# reg-board-1.net
KiCad netlist of a schematic drawn in EAGLE
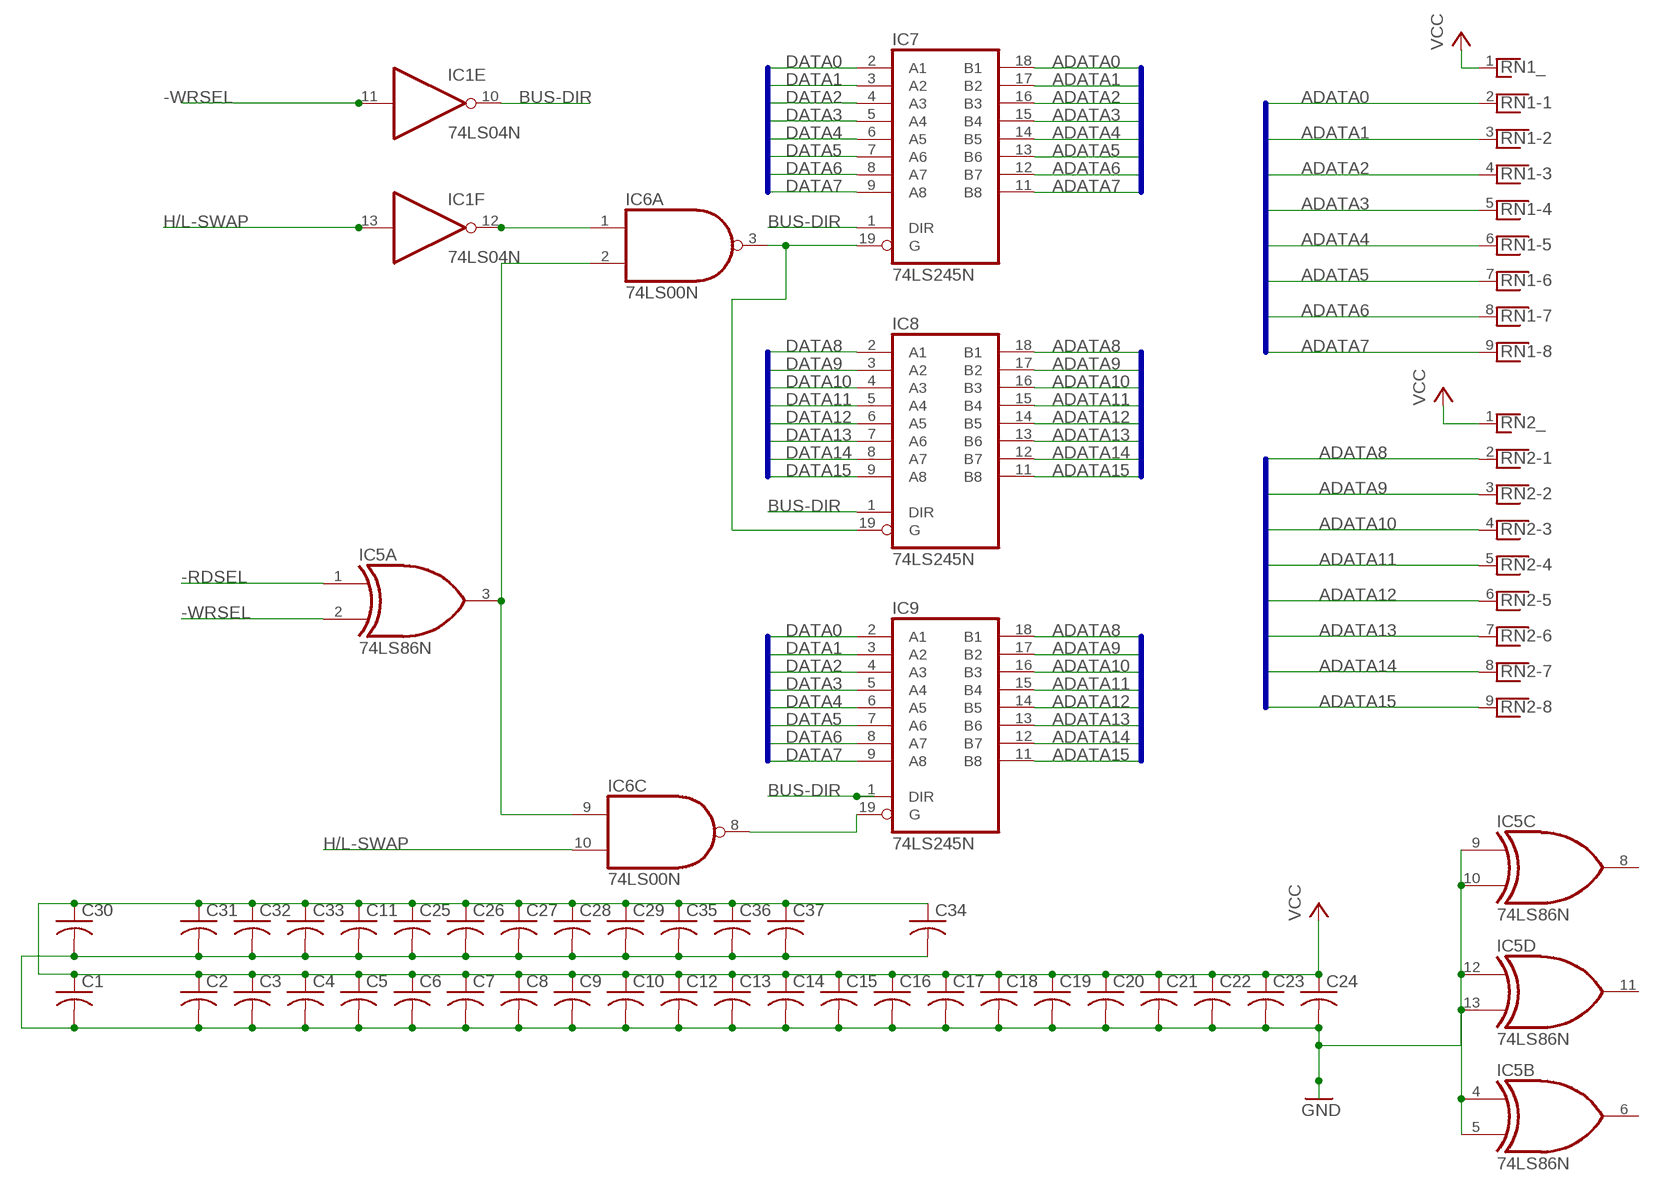
[diagram p0: schematic, sheet 1]
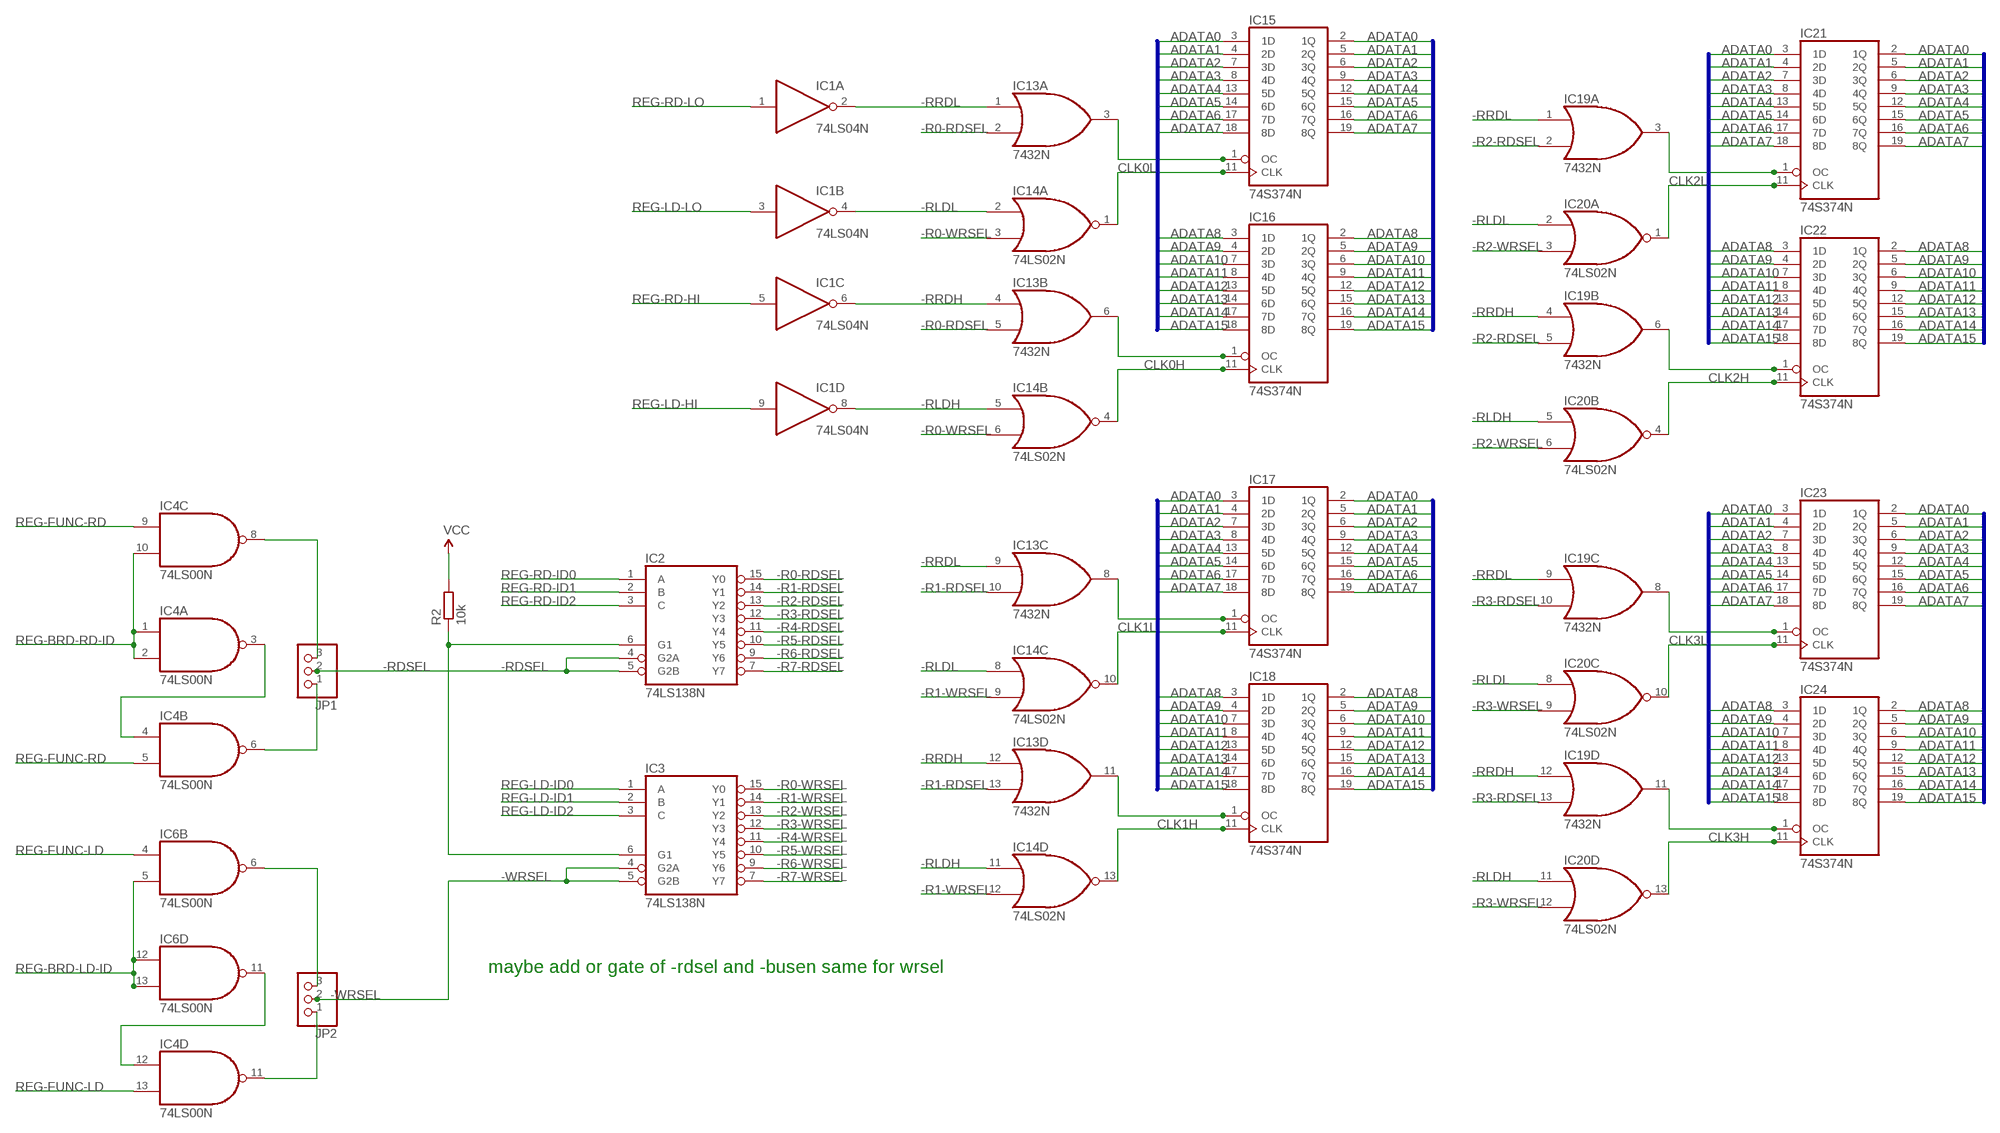
[diagram p1: schematic, sheet 2]
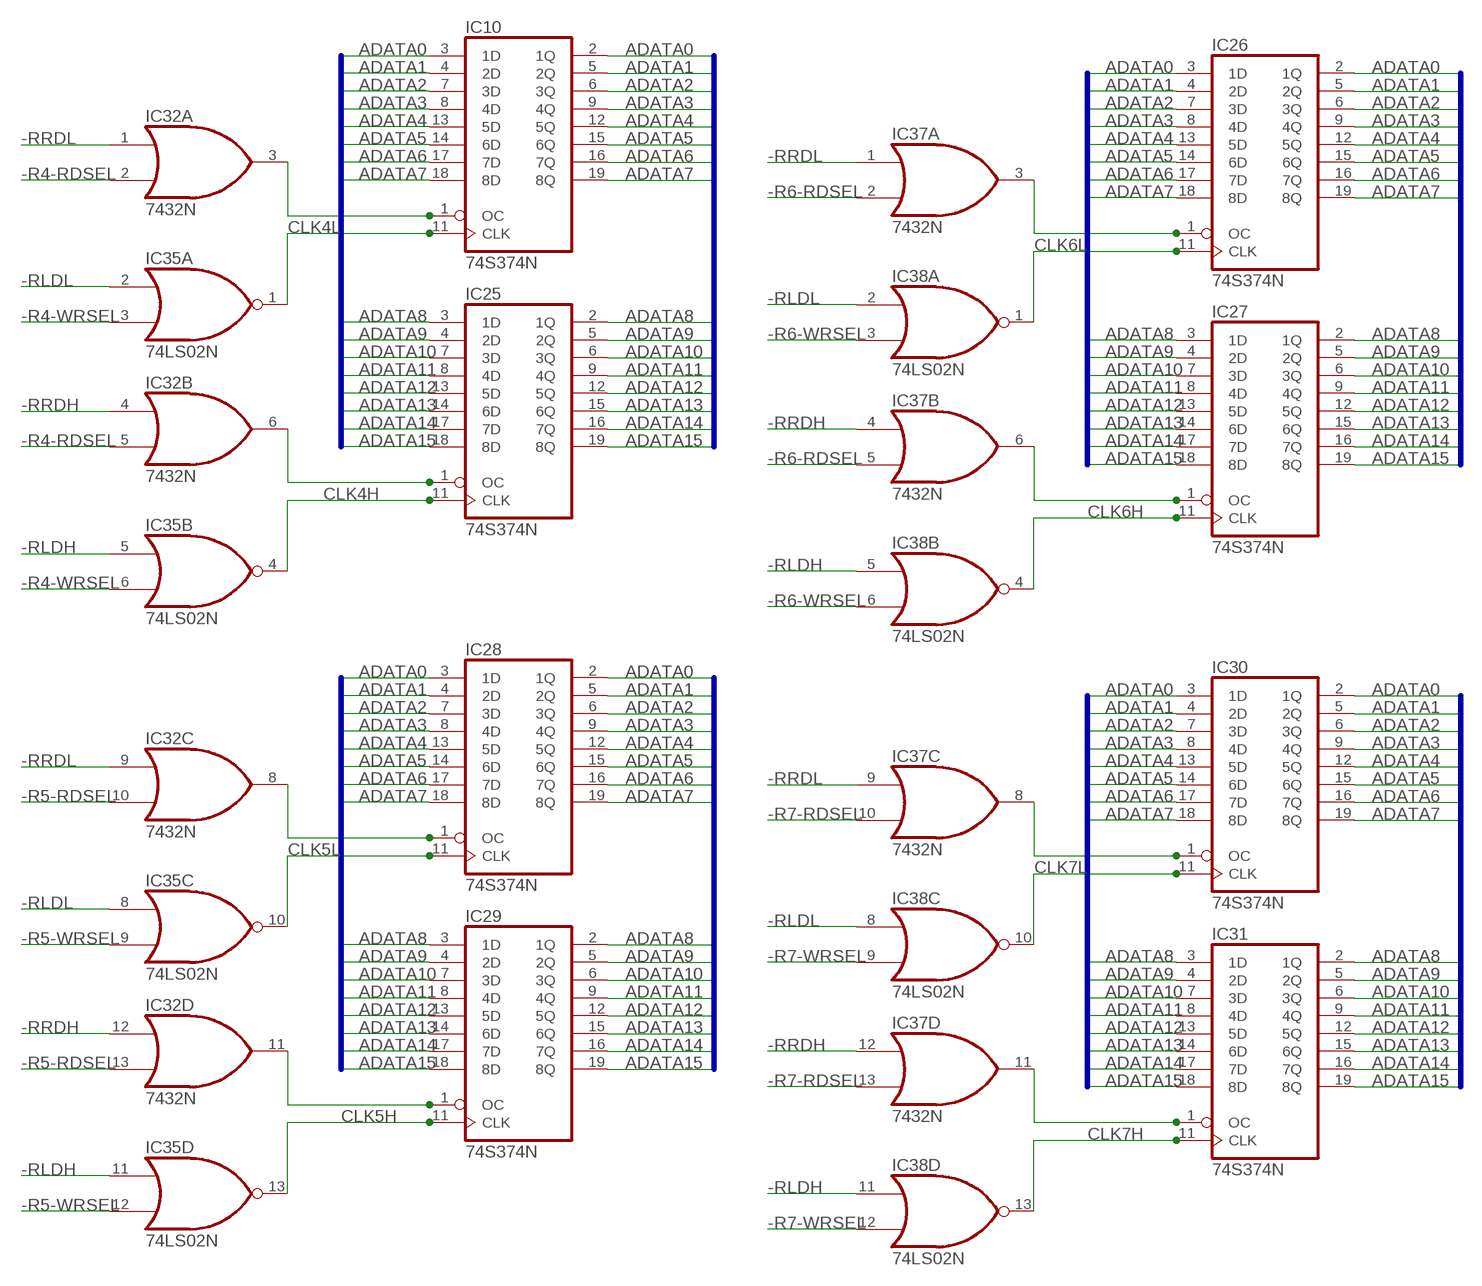
[diagram p2: schematic, sheet 3]
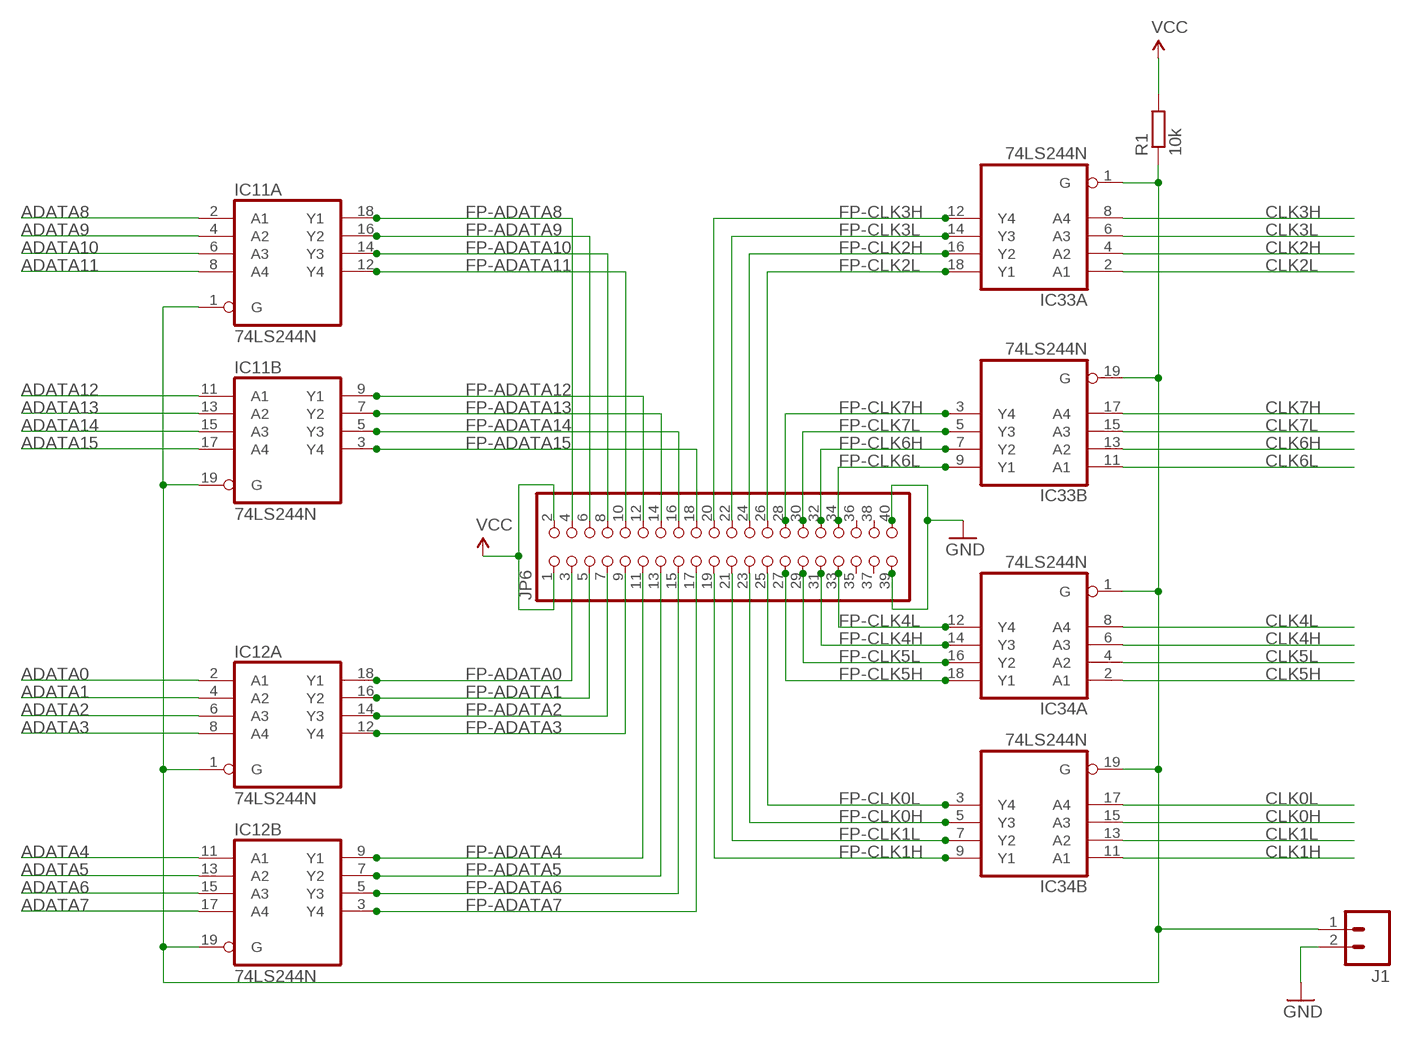
[diagram p3: schematic, sheet 4]
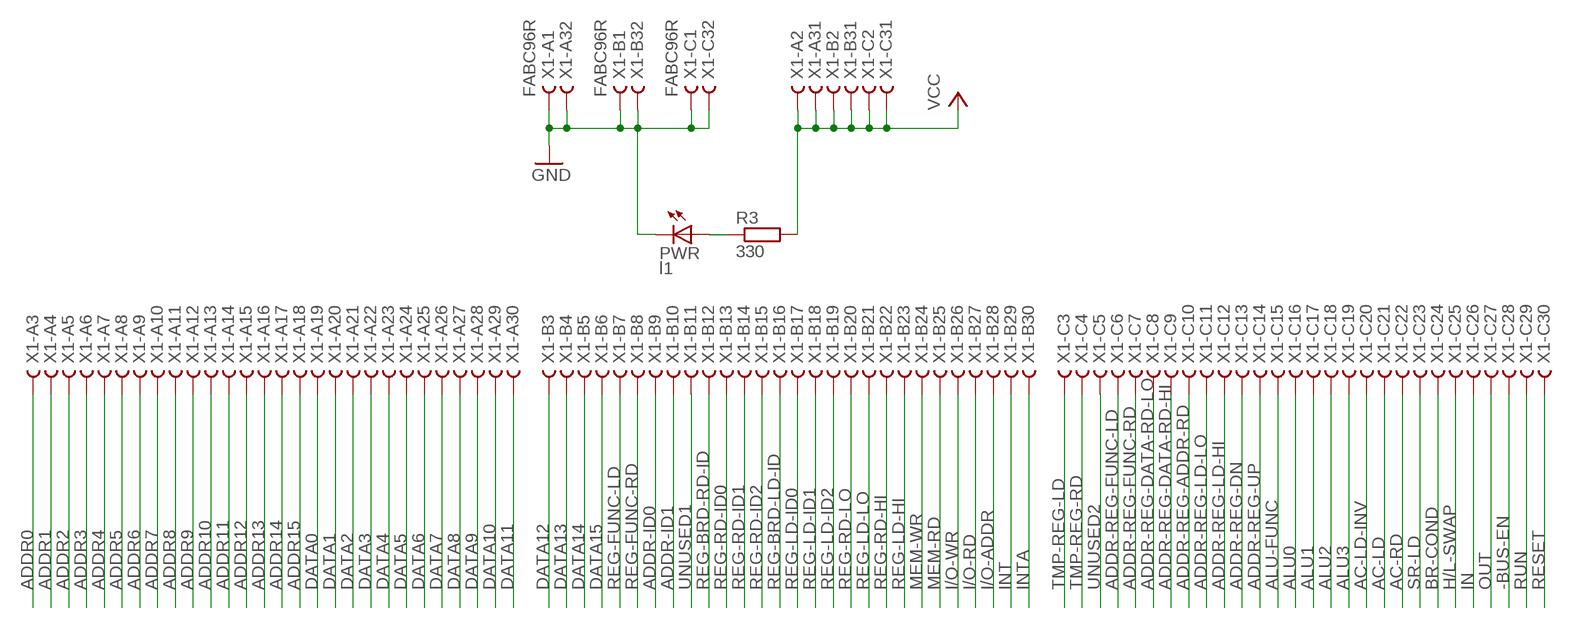
[diagram p4: schematic, sheet 5]

(export (version "E")
  (design (tool "Eeschema 10.0.6"))
  (components
    (comp (ref "IC10")
      (value "74S374N")
      (footprint "eagle-import:DIL20")
      (libsource (lib "eagle-import") (part "74374NS"))
    )
    (comp (ref "IC25")
      (value "74S374N")
      (footprint "eagle-import:DIL20")
      (libsource (lib "eagle-import") (part "74374NS"))
    )
    (comp (ref "IC26")
      (value "74S374N")
      (footprint "eagle-import:DIL20")
      (libsource (lib "eagle-import") (part "74374NS"))
    )
    (comp (ref "IC27")
      (value "74S374N")
      (footprint "eagle-import:DIL20")
      (libsource (lib "eagle-import") (part "74374NS"))
    )
    (comp (ref "IC28")
      (value "74S374N")
      (footprint "eagle-import:DIL20")
      (libsource (lib "eagle-import") (part "74374NS"))
    )
    (comp (ref "IC29")
      (value "74S374N")
      (footprint "eagle-import:DIL20")
      (libsource (lib "eagle-import") (part "74374NS"))
    )
    (comp (ref "IC30")
      (value "74S374N")
      (footprint "eagle-import:DIL20")
      (libsource (lib "eagle-import") (part "74374NS"))
    )
    (comp (ref "IC31")
      (value "74S374N")
      (footprint "eagle-import:DIL20")
      (libsource (lib "eagle-import") (part "74374NS"))
    )
    (comp (ref "IC32")
      (value "7432N")
      (footprint "eagle-import:DIL14")
      (libsource (lib "eagle-import") (part "7432N"))
    )
    (comp (ref "IC35")
      (value "74LS02N")
      (footprint "eagle-import:DIL14")
      (libsource (lib "eagle-import") (part "7402NLS"))
    )
    (comp (ref "IC37")
      (value "7432N")
      (footprint "eagle-import:DIL14")
      (libsource (lib "eagle-import") (part "7432N"))
    )
    (comp (ref "IC38")
      (value "74LS02N")
      (footprint "eagle-import:DIL14")
      (libsource (lib "eagle-import") (part "7402NLS"))
    )
    (comp (ref "IC1")
      (value "74LS04N")
      (footprint "eagle-import:DIL14")
      (libsource (lib "eagle-import") (part "7404NLS"))
    )
    (comp (ref "IC2")
      (value "74LS138N")
      (footprint "eagle-import:DIL16")
      (libsource (lib "eagle-import") (part "74138NLS"))
    )
    (comp (ref "IC3")
      (value "74LS138N")
      (footprint "eagle-import:DIL16")
      (libsource (lib "eagle-import") (part "74138NLS"))
    )
    (comp (ref "IC4")
      (value "74LS00N")
      (footprint "eagle-import:DIL14")
      (libsource (lib "eagle-import") (part "7400NLS"))
    )
    (comp (ref "IC6")
      (value "74LS00N")
      (footprint "eagle-import:DIL14")
      (libsource (lib "eagle-import") (part "7400NLS"))
    )
    (comp (ref "IC13")
      (value "7432N")
      (footprint "eagle-import:DIL14")
      (libsource (lib "eagle-import") (part "7432N"))
    )
    (comp (ref "IC14")
      (value "74LS02N")
      (footprint "eagle-import:DIL14")
      (libsource (lib "eagle-import") (part "7402NLS"))
    )
    (comp (ref "IC15")
      (value "74S374N")
      (footprint "eagle-import:DIL20")
      (libsource (lib "eagle-import") (part "74374NS"))
    )
    (comp (ref "IC16")
      (value "74S374N")
      (footprint "eagle-import:DIL20")
      (libsource (lib "eagle-import") (part "74374NS"))
    )
    (comp (ref "IC17")
      (value "74S374N")
      (footprint "eagle-import:DIL20")
      (libsource (lib "eagle-import") (part "74374NS"))
    )
    (comp (ref "IC18")
      (value "74S374N")
      (footprint "eagle-import:DIL20")
      (libsource (lib "eagle-import") (part "74374NS"))
    )
    (comp (ref "IC19")
      (value "7432N")
      (footprint "eagle-import:DIL14")
      (libsource (lib "eagle-import") (part "7432N"))
    )
    (comp (ref "IC20")
      (value "74LS02N")
      (footprint "eagle-import:DIL14")
      (libsource (lib "eagle-import") (part "7402NLS"))
    )
    (comp (ref "IC21")
      (value "74S374N")
      (footprint "eagle-import:DIL20")
      (libsource (lib "eagle-import") (part "74374NS"))
    )
    (comp (ref "IC22")
      (value "74S374N")
      (footprint "eagle-import:DIL20")
      (libsource (lib "eagle-import") (part "74374NS"))
    )
    (comp (ref "IC23")
      (value "74S374N")
      (footprint "eagle-import:DIL20")
      (libsource (lib "eagle-import") (part "74374NS"))
    )
    (comp (ref "IC24")
      (value "74S374N")
      (footprint "eagle-import:DIL20")
      (libsource (lib "eagle-import") (part "74374NS"))
    )
    (comp (ref "JP1")
      (value "PINHD-1X3")
      (footprint "eagle-import:1X03")
      (libsource (lib "eagle-import") (part "PINHD-1X3"))
    )
    (comp (ref "JP2")
      (value "PINHD-1X3")
      (footprint "eagle-import:1X03")
      (libsource (lib "eagle-import") (part "PINHD-1X3"))
    )
    (comp (ref "R2")
      (value "10k")
      (footprint "eagle-import:0207_10")
      (libsource (lib "eagle-import") (part "R0207/10"))
    )
    (comp (ref "PWR")
      (value "l1")
      (footprint "eagle-import:LED5MM")
      (libsource (lib "eagle-import") (part "LED5MM"))
    )
    (comp (ref "R3")
      (value "330")
      (footprint "eagle-import:0207_10")
      (libsource (lib "eagle-import") (part "R0207/10"))
    )
    (comp (ref "X1")
      (value "FABC96R")
      (footprint "eagle-import:FABC96R")
      (libsource (lib "eagle-import") (part "FABC96R"))
    )
    (comp (ref "IC11")
      (value "74LS244N")
      (footprint "eagle-import:DIL20")
      (libsource (lib "eagle-import") (part "74xx-us_74244NLS"))
    )
    (comp (ref "IC12")
      (value "74LS244N")
      (footprint "eagle-import:DIL20")
      (libsource (lib "eagle-import") (part "74xx-us_74244NLS"))
    )
    (comp (ref "IC33")
      (value "74LS244N")
      (footprint "eagle-import:DIL20")
      (libsource (lib "eagle-import") (part "74xx-us_74244NLS"))
    )
    (comp (ref "IC34")
      (value "74LS244N")
      (footprint "eagle-import:DIL20")
      (libsource (lib "eagle-import") (part "74xx-us_74244NLS"))
    )
    (comp (ref "J1")
      (value "M02PTH")
      (footprint "eagle-import:1X02")
      (libsource (lib "eagle-import") (part "M02PTH"))
    )
    (comp (ref "JP6")
      (value "PINHD-2X20")
      (footprint "eagle-import:2X20")
      (libsource (lib "eagle-import") (part "PINHD-2X20"))
    )
    (comp (ref "R1")
      (value "10k")
      (footprint "eagle-import:0207_10")
      (libsource (lib "eagle-import") (part "R0207/10"))
    )
    (comp (ref "C1")
      (value "C-US025-040X050")
      (footprint "eagle-import:C025-040X050")
      (libsource (lib "eagle-import") (part "C-US025-040X050"))
    )
    (comp (ref "C2")
      (value "C-US025-040X050")
      (footprint "eagle-import:C025-040X050")
      (libsource (lib "eagle-import") (part "C-US025-040X050"))
    )
    (comp (ref "C3")
      (value "C-US025-040X050")
      (footprint "eagle-import:C025-040X050")
      (libsource (lib "eagle-import") (part "C-US025-040X050"))
    )
    (comp (ref "C4")
      (value "C-US025-040X050")
      (footprint "eagle-import:C025-040X050")
      (libsource (lib "eagle-import") (part "C-US025-040X050"))
    )
    (comp (ref "C5")
      (value "C-US025-040X050")
      (footprint "eagle-import:C025-040X050")
      (libsource (lib "eagle-import") (part "C-US025-040X050"))
    )
    (comp (ref "C6")
      (value "C-US025-040X050")
      (footprint "eagle-import:C025-040X050")
      (libsource (lib "eagle-import") (part "C-US025-040X050"))
    )
    (comp (ref "C7")
      (value "C-US025-040X050")
      (footprint "eagle-import:C025-040X050")
      (libsource (lib "eagle-import") (part "C-US025-040X050"))
    )
    (comp (ref "C8")
      (value "C-US025-040X050")
      (footprint "eagle-import:C025-040X050")
      (libsource (lib "eagle-import") (part "C-US025-040X050"))
    )
    (comp (ref "C9")
      (value "C-US025-040X050")
      (footprint "eagle-import:C025-040X050")
      (libsource (lib "eagle-import") (part "C-US025-040X050"))
    )
    (comp (ref "C10")
      (value "C-US025-040X050")
      (footprint "eagle-import:C025-040X050")
      (libsource (lib "eagle-import") (part "C-US025-040X050"))
    )
    (comp (ref "C11")
      (value "C-US025-040X050")
      (footprint "eagle-import:C025-040X050")
      (libsource (lib "eagle-import") (part "C-US025-040X050"))
    )
    (comp (ref "C12")
      (value "C-US025-040X050")
      (footprint "eagle-import:C025-040X050")
      (libsource (lib "eagle-import") (part "C-US025-040X050"))
    )
    (comp (ref "C13")
      (value "C-US025-040X050")
      (footprint "eagle-import:C025-040X050")
      (libsource (lib "eagle-import") (part "C-US025-040X050"))
    )
    (comp (ref "C14")
      (value "C-US025-040X050")
      (footprint "eagle-import:C025-040X050")
      (libsource (lib "eagle-import") (part "C-US025-040X050"))
    )
    (comp (ref "C15")
      (value "C-US025-040X050")
      (footprint "eagle-import:C025-040X050")
      (libsource (lib "eagle-import") (part "C-US025-040X050"))
    )
    (comp (ref "C16")
      (value "C-US025-040X050")
      (footprint "eagle-import:C025-040X050")
      (libsource (lib "eagle-import") (part "C-US025-040X050"))
    )
    (comp (ref "C17")
      (value "C-US025-040X050")
      (footprint "eagle-import:C025-040X050")
      (libsource (lib "eagle-import") (part "C-US025-040X050"))
    )
    (comp (ref "C18")
      (value "C-US025-040X050")
      (footprint "eagle-import:C025-040X050")
      (libsource (lib "eagle-import") (part "C-US025-040X050"))
    )
    (comp (ref "C19")
      (value "C-US025-040X050")
      (footprint "eagle-import:C025-040X050")
      (libsource (lib "eagle-import") (part "C-US025-040X050"))
    )
    (comp (ref "C20")
      (value "C-US025-040X050")
      (footprint "eagle-import:C025-040X050")
      (libsource (lib "eagle-import") (part "C-US025-040X050"))
    )
    (comp (ref "C21")
      (value "C-US025-040X050")
      (footprint "eagle-import:C025-040X050")
      (libsource (lib "eagle-import") (part "C-US025-040X050"))
    )
    (comp (ref "C22")
      (value "C-US025-040X050")
      (footprint "eagle-import:C025-040X050")
      (libsource (lib "eagle-import") (part "C-US025-040X050"))
    )
    (comp (ref "C23")
      (value "C-US025-040X050")
      (footprint "eagle-import:C025-040X050")
      (libsource (lib "eagle-import") (part "C-US025-040X050"))
    )
    (comp (ref "C24")
      (value "C-US025-040X050")
      (footprint "eagle-import:C025-040X050")
      (libsource (lib "eagle-import") (part "C-US025-040X050"))
    )
    (comp (ref "C25")
      (value "C-US025-040X050")
      (footprint "eagle-import:C025-040X050")
      (libsource (lib "eagle-import") (part "C-US025-040X050"))
    )
    (comp (ref "C26")
      (value "C-US025-040X050")
      (footprint "eagle-import:C025-040X050")
      (libsource (lib "eagle-import") (part "C-US025-040X050"))
    )
    (comp (ref "C27")
      (value "C-US025-040X050")
      (footprint "eagle-import:C025-040X050")
      (libsource (lib "eagle-import") (part "C-US025-040X050"))
    )
    (comp (ref "C28")
      (value "C-US025-040X050")
      (footprint "eagle-import:C025-040X050")
      (libsource (lib "eagle-import") (part "C-US025-040X050"))
    )
    (comp (ref "C29")
      (value "C-US025-040X050")
      (footprint "eagle-import:C025-040X050")
      (libsource (lib "eagle-import") (part "C-US025-040X050"))
    )
    (comp (ref "C30")
      (value "C-US025-040X050")
      (footprint "eagle-import:C025-040X050")
      (libsource (lib "eagle-import") (part "C-US025-040X050"))
    )
    (comp (ref "C31")
      (value "C-US025-040X050")
      (footprint "eagle-import:C025-040X050")
      (libsource (lib "eagle-import") (part "C-US025-040X050"))
    )
    (comp (ref "C32")
      (value "C-US025-040X050")
      (footprint "eagle-import:C025-040X050")
      (libsource (lib "eagle-import") (part "C-US025-040X050"))
    )
    (comp (ref "C33")
      (value "C-US025-040X050")
      (footprint "eagle-import:C025-040X050")
      (libsource (lib "eagle-import") (part "C-US025-040X050"))
    )
    (comp (ref "C34")
      (value "C-US025-040X050")
      (footprint "eagle-import:C025-040X050")
      (libsource (lib "eagle-import") (part "C-US025-040X050"))
    )
    (comp (ref "C35")
      (value "C-US025-040X050")
      (footprint "eagle-import:C025-040X050")
      (libsource (lib "eagle-import") (part "C-US025-040X050"))
    )
    (comp (ref "C36")
      (value "C-US025-040X050")
      (footprint "eagle-import:C025-040X050")
      (libsource (lib "eagle-import") (part "C-US025-040X050"))
    )
    (comp (ref "C37")
      (value "C-US025-040X050")
      (footprint "eagle-import:C025-040X050")
      (libsource (lib "eagle-import") (part "C-US025-040X050"))
    )
    (comp (ref "IC5")
      (value "74LS86N")
      (footprint "eagle-import:DIL14")
      (libsource (lib "eagle-import") (part "7486NLS"))
    )
    (comp (ref "IC7")
      (value "74LS245N")
      (footprint "eagle-import:DIL20")
      (libsource (lib "eagle-import") (part "74245NLS"))
    )
    (comp (ref "IC8")
      (value "74LS245N")
      (footprint "eagle-import:DIL20")
      (libsource (lib "eagle-import") (part "74245NLS"))
    )
    (comp (ref "IC9")
      (value "74LS245N")
      (footprint "eagle-import:DIL20")
      (libsource (lib "eagle-import") (part "74245NLS"))
    )
    (comp (ref "RN1")
      (value "RNX8")
      (footprint "eagle-import:RN-9")
      (libsource (lib "eagle-import") (part "RNX8"))
    )
    (comp (ref "RN2")
      (value "RNX8")
      (footprint "eagle-import:RN-9")
      (libsource (lib "eagle-import") (part "RNX8"))
    )
  )
  (nets
    (net (code "1") (name "-BUS-EN") (class "Default")
      (node (ref "X1") (pin "C28") (pinfunction "B_C28") (pintype "passive"))
    )
    (net (code "2") (name "-R0-RDSEL") (class "Default")
      (node (ref "IC13") (pin "2") (pinfunction "I1_2") (pintype "input"))
      (node (ref "IC13") (pin "5") (pinfunction "I1_5") (pintype "input"))
      (node (ref "IC2") (pin "15") (pinfunction "Y0_15") (pintype "output"))
    )
    (net (code "3") (name "-R0-WRSEL") (class "Default")
      (node (ref "IC14") (pin "3") (pinfunction "I1_3") (pintype "input"))
      (node (ref "IC14") (pin "6") (pinfunction "I1_6") (pintype "input"))
      (node (ref "IC3") (pin "15") (pinfunction "Y0_15") (pintype "output"))
    )
    (net (code "4") (name "-R1-RDSEL") (class "Default")
      (node (ref "IC13") (pin "10") (pinfunction "I1_10") (pintype "input"))
      (node (ref "IC13") (pin "13") (pinfunction "I1_13") (pintype "input"))
      (node (ref "IC2") (pin "14") (pinfunction "Y1_14") (pintype "output"))
    )
    (net (code "5") (name "-R1-WRSEL") (class "Default")
      (node (ref "IC14") (pin "12") (pinfunction "I1_12") (pintype "input"))
      (node (ref "IC14") (pin "9") (pinfunction "I1_9") (pintype "input"))
      (node (ref "IC3") (pin "14") (pinfunction "Y1_14") (pintype "output"))
    )
    (net (code "6") (name "-R2-RDSEL") (class "Default")
      (node (ref "IC19") (pin "2") (pinfunction "I1_2") (pintype "input"))
      (node (ref "IC19") (pin "5") (pinfunction "I1_5") (pintype "input"))
      (node (ref "IC2") (pin "13") (pinfunction "Y2_13") (pintype "output"))
    )
    (net (code "7") (name "-R2-WRSEL") (class "Default")
      (node (ref "IC20") (pin "3") (pinfunction "I1_3") (pintype "input"))
      (node (ref "IC20") (pin "6") (pinfunction "I1_6") (pintype "input"))
      (node (ref "IC3") (pin "13") (pinfunction "Y2_13") (pintype "output"))
    )
    (net (code "8") (name "-R3-RDSEL") (class "Default")
      (node (ref "IC19") (pin "10") (pinfunction "I1_10") (pintype "input"))
      (node (ref "IC19") (pin "13") (pinfunction "I1_13") (pintype "input"))
      (node (ref "IC2") (pin "12") (pinfunction "Y3_12") (pintype "output"))
    )
    (net (code "9") (name "-R3-WRSEL") (class "Default")
      (node (ref "IC20") (pin "12") (pinfunction "I1_12") (pintype "input"))
      (node (ref "IC20") (pin "9") (pinfunction "I1_9") (pintype "input"))
      (node (ref "IC3") (pin "12") (pinfunction "Y3_12") (pintype "output"))
    )
    (net (code "10") (name "-R4-RDSEL") (class "Default")
      (node (ref "IC2") (pin "11") (pinfunction "Y4_11") (pintype "output"))
      (node (ref "IC32") (pin "2") (pinfunction "I1_2") (pintype "input"))
      (node (ref "IC32") (pin "5") (pinfunction "I1_5") (pintype "input"))
    )
    (net (code "11") (name "-R4-WRSEL") (class "Default")
      (node (ref "IC3") (pin "11") (pinfunction "Y4_11") (pintype "output"))
      (node (ref "IC35") (pin "3") (pinfunction "I1_3") (pintype "input"))
      (node (ref "IC35") (pin "6") (pinfunction "I1_6") (pintype "input"))
    )
    (net (code "12") (name "-R5-RDSEL") (class "Default")
      (node (ref "IC2") (pin "10") (pinfunction "Y5_10") (pintype "output"))
      (node (ref "IC32") (pin "10") (pinfunction "I1_10") (pintype "input"))
      (node (ref "IC32") (pin "13") (pinfunction "I1_13") (pintype "input"))
    )
    (net (code "13") (name "-R5-WRSEL") (class "Default")
      (node (ref "IC3") (pin "10") (pinfunction "Y5_10") (pintype "output"))
      (node (ref "IC35") (pin "12") (pinfunction "I1_12") (pintype "input"))
      (node (ref "IC35") (pin "9") (pinfunction "I1_9") (pintype "input"))
    )
    (net (code "14") (name "-R6-RDSEL") (class "Default")
      (node (ref "IC2") (pin "9") (pinfunction "Y6_9") (pintype "output"))
      (node (ref "IC37") (pin "2") (pinfunction "I1_2") (pintype "input"))
      (node (ref "IC37") (pin "5") (pinfunction "I1_5") (pintype "input"))
    )
    (net (code "15") (name "-R6-WRSEL") (class "Default")
      (node (ref "IC3") (pin "9") (pinfunction "Y6_9") (pintype "output"))
      (node (ref "IC38") (pin "3") (pinfunction "I1_3") (pintype "input"))
      (node (ref "IC38") (pin "6") (pinfunction "I1_6") (pintype "input"))
    )
    (net (code "16") (name "-R7-RDSEL") (class "Default")
      (node (ref "IC2") (pin "7") (pinfunction "Y7_7") (pintype "output"))
      (node (ref "IC37") (pin "10") (pinfunction "I1_10") (pintype "input"))
      (node (ref "IC37") (pin "13") (pinfunction "I1_13") (pintype "input"))
    )
    (net (code "17") (name "-R7-WRSEL") (class "Default")
      (node (ref "IC3") (pin "7") (pinfunction "Y7_7") (pintype "output"))
      (node (ref "IC38") (pin "12") (pinfunction "I1_12") (pintype "input"))
      (node (ref "IC38") (pin "9") (pinfunction "I1_9") (pintype "input"))
    )
    (net (code "18") (name "-RDSEL") (class "Default")
      (node (ref "IC2") (pin "4") (pinfunction "G2A_4") (pintype "input"))
      (node (ref "IC2") (pin "5") (pinfunction "G2B_5") (pintype "input"))
      (node (ref "IC5") (pin "1") (pinfunction "I0_1") (pintype "input"))
      (node (ref "JP1") (pin "2") (pinfunction "2_2") (pintype "passive"))
    )
    (net (code "19") (name "-RLDH") (class "Default")
      (node (ref "IC1") (pin "8") (pinfunction "O_8") (pintype "output"))
      (node (ref "IC14") (pin "11") (pinfunction "I0_11") (pintype "input"))
      (node (ref "IC14") (pin "5") (pinfunction "I0_5") (pintype "input"))
      (node (ref "IC20") (pin "11") (pinfunction "I0_11") (pintype "input"))
      (node (ref "IC20") (pin "5") (pinfunction "I0_5") (pintype "input"))
      (node (ref "IC35") (pin "11") (pinfunction "I0_11") (pintype "input"))
      (node (ref "IC35") (pin "5") (pinfunction "I0_5") (pintype "input"))
      (node (ref "IC38") (pin "11") (pinfunction "I0_11") (pintype "input"))
      (node (ref "IC38") (pin "5") (pinfunction "I0_5") (pintype "input"))
    )
    (net (code "20") (name "-RLDL") (class "Default")
      (node (ref "IC1") (pin "4") (pinfunction "O_4") (pintype "output"))
      (node (ref "IC14") (pin "2") (pinfunction "I0_2") (pintype "input"))
      (node (ref "IC14") (pin "8") (pinfunction "I0_8") (pintype "input"))
      (node (ref "IC20") (pin "2") (pinfunction "I0_2") (pintype "input"))
      (node (ref "IC20") (pin "8") (pinfunction "I0_8") (pintype "input"))
      (node (ref "IC35") (pin "2") (pinfunction "I0_2") (pintype "input"))
      (node (ref "IC35") (pin "8") (pinfunction "I0_8") (pintype "input"))
      (node (ref "IC38") (pin "2") (pinfunction "I0_2") (pintype "input"))
      (node (ref "IC38") (pin "8") (pinfunction "I0_8") (pintype "input"))
    )
    (net (code "21") (name "-RRDH") (class "Default")
      (node (ref "IC1") (pin "6") (pinfunction "O_6") (pintype "output"))
      (node (ref "IC13") (pin "12") (pinfunction "I0_12") (pintype "input"))
      (node (ref "IC13") (pin "4") (pinfunction "I0_4") (pintype "input"))
      (node (ref "IC19") (pin "12") (pinfunction "I0_12") (pintype "input"))
      (node (ref "IC19") (pin "4") (pinfunction "I0_4") (pintype "input"))
      (node (ref "IC32") (pin "12") (pinfunction "I0_12") (pintype "input"))
      (node (ref "IC32") (pin "4") (pinfunction "I0_4") (pintype "input"))
      (node (ref "IC37") (pin "12") (pinfunction "I0_12") (pintype "input"))
      (node (ref "IC37") (pin "4") (pinfunction "I0_4") (pintype "input"))
    )
    (net (code "22") (name "-RRDL") (class "Default")
      (node (ref "IC1") (pin "2") (pinfunction "O_2") (pintype "output"))
      (node (ref "IC13") (pin "1") (pinfunction "I0_1") (pintype "input"))
      (node (ref "IC13") (pin "9") (pinfunction "I0_9") (pintype "input"))
      (node (ref "IC19") (pin "1") (pinfunction "I0_1") (pintype "input"))
      (node (ref "IC19") (pin "9") (pinfunction "I0_9") (pintype "input"))
      (node (ref "IC32") (pin "1") (pinfunction "I0_1") (pintype "input"))
      (node (ref "IC32") (pin "9") (pinfunction "I0_9") (pintype "input"))
      (node (ref "IC37") (pin "1") (pinfunction "I0_1") (pintype "input"))
      (node (ref "IC37") (pin "9") (pinfunction "I0_9") (pintype "input"))
    )
    (net (code "23") (name "-WRSEL") (class "Default")
      (node (ref "IC1") (pin "11") (pinfunction "I_11") (pintype "input"))
      (node (ref "IC3") (pin "4") (pinfunction "G2A_4") (pintype "input"))
      (node (ref "IC3") (pin "5") (pinfunction "G2B_5") (pintype "input"))
      (node (ref "IC5") (pin "2") (pinfunction "I1_2") (pintype "input"))
      (node (ref "JP2") (pin "2") (pinfunction "2_2") (pintype "passive"))
    )
    (net (code "24") (name "AC-LD") (class "Default")
      (node (ref "X1") (pin "C21") (pinfunction "B_C21") (pintype "passive"))
    )
    (net (code "25") (name "AC-LD-INV") (class "Default")
      (node (ref "X1") (pin "C20") (pinfunction "B_C20") (pintype "passive"))
    )
    (net (code "26") (name "AC-RD") (class "Default")
      (node (ref "X1") (pin "C22") (pinfunction "B_C22") (pintype "passive"))
    )
    (net (code "27") (name "ADATA0") (class "Default")
      (node (ref "IC10") (pin "2") (pinfunction "1Q_2") (pintype "tri_state"))
      (node (ref "IC10") (pin "3") (pinfunction "1D_3") (pintype "input"))
      (node (ref "IC12") (pin "2") (pinfunction "A1_2") (pintype "input"))
      (node (ref "IC15") (pin "2") (pinfunction "1Q_2") (pintype "tri_state"))
      (node (ref "IC15") (pin "3") (pinfunction "1D_3") (pintype "input"))
      (node (ref "IC17") (pin "2") (pinfunction "1Q_2") (pintype "tri_state"))
      (node (ref "IC17") (pin "3") (pinfunction "1D_3") (pintype "input"))
      (node (ref "IC21") (pin "2") (pinfunction "1Q_2") (pintype "tri_state"))
      (node (ref "IC21") (pin "3") (pinfunction "1D_3") (pintype "input"))
      (node (ref "IC23") (pin "2") (pinfunction "1Q_2") (pintype "tri_state"))
      (node (ref "IC23") (pin "3") (pinfunction "1D_3") (pintype "input"))
      (node (ref "IC26") (pin "2") (pinfunction "1Q_2") (pintype "tri_state"))
      (node (ref "IC26") (pin "3") (pinfunction "1D_3") (pintype "input"))
      (node (ref "IC28") (pin "2") (pinfunction "1Q_2") (pintype "tri_state"))
      (node (ref "IC28") (pin "3") (pinfunction "1D_3") (pintype "input"))
      (node (ref "IC30") (pin "2") (pinfunction "1Q_2") (pintype "tri_state"))
      (node (ref "IC30") (pin "3") (pinfunction "1D_3") (pintype "input"))
      (node (ref "IC7") (pin "18") (pinfunction "B1_18") (pintype "bidirectional"))
      (node (ref "RN1") (pin "2") (pinfunction "1_2") (pintype "passive"))
    )
    (net (code "28") (name "ADATA1") (class "Default")
      (node (ref "IC10") (pin "4") (pinfunction "2D_4") (pintype "input"))
      (node (ref "IC10") (pin "5") (pinfunction "2Q_5") (pintype "tri_state"))
      (node (ref "IC12") (pin "4") (pinfunction "A2_4") (pintype "input"))
      (node (ref "IC15") (pin "4") (pinfunction "2D_4") (pintype "input"))
      (node (ref "IC15") (pin "5") (pinfunction "2Q_5") (pintype "tri_state"))
      (node (ref "IC17") (pin "4") (pinfunction "2D_4") (pintype "input"))
      (node (ref "IC17") (pin "5") (pinfunction "2Q_5") (pintype "tri_state"))
      (node (ref "IC21") (pin "4") (pinfunction "2D_4") (pintype "input"))
      (node (ref "IC21") (pin "5") (pinfunction "2Q_5") (pintype "tri_state"))
      (node (ref "IC23") (pin "4") (pinfunction "2D_4") (pintype "input"))
      (node (ref "IC23") (pin "5") (pinfunction "2Q_5") (pintype "tri_state"))
      (node (ref "IC26") (pin "4") (pinfunction "2D_4") (pintype "input"))
      (node (ref "IC26") (pin "5") (pinfunction "2Q_5") (pintype "tri_state"))
      (node (ref "IC28") (pin "4") (pinfunction "2D_4") (pintype "input"))
      (node (ref "IC28") (pin "5") (pinfunction "2Q_5") (pintype "tri_state"))
      (node (ref "IC30") (pin "4") (pinfunction "2D_4") (pintype "input"))
      (node (ref "IC30") (pin "5") (pinfunction "2Q_5") (pintype "tri_state"))
      (node (ref "IC7") (pin "17") (pinfunction "B2_17") (pintype "bidirectional"))
      (node (ref "RN1") (pin "3") (pinfunction "1_3") (pintype "passive"))
    )
    (net (code "29") (name "ADATA2") (class "Default")
      (node (ref "IC10") (pin "6") (pinfunction "3Q_6") (pintype "tri_state"))
      (node (ref "IC10") (pin "7") (pinfunction "3D_7") (pintype "input"))
      (node (ref "IC12") (pin "6") (pinfunction "A3_6") (pintype "input"))
      (node (ref "IC15") (pin "6") (pinfunction "3Q_6") (pintype "tri_state"))
      (node (ref "IC15") (pin "7") (pinfunction "3D_7") (pintype "input"))
      (node (ref "IC17") (pin "6") (pinfunction "3Q_6") (pintype "tri_state"))
      (node (ref "IC17") (pin "7") (pinfunction "3D_7") (pintype "input"))
      (node (ref "IC21") (pin "6") (pinfunction "3Q_6") (pintype "tri_state"))
      (node (ref "IC21") (pin "7") (pinfunction "3D_7") (pintype "input"))
      (node (ref "IC23") (pin "6") (pinfunction "3Q_6") (pintype "tri_state"))
      (node (ref "IC23") (pin "7") (pinfunction "3D_7") (pintype "input"))
      (node (ref "IC26") (pin "6") (pinfunction "3Q_6") (pintype "tri_state"))
      (node (ref "IC26") (pin "7") (pinfunction "3D_7") (pintype "input"))
      (node (ref "IC28") (pin "6") (pinfunction "3Q_6") (pintype "tri_state"))
      (node (ref "IC28") (pin "7") (pinfunction "3D_7") (pintype "input"))
      (node (ref "IC30") (pin "6") (pinfunction "3Q_6") (pintype "tri_state"))
      (node (ref "IC30") (pin "7") (pinfunction "3D_7") (pintype "input"))
      (node (ref "IC7") (pin "16") (pinfunction "B3_16") (pintype "bidirectional"))
      (node (ref "RN1") (pin "4") (pinfunction "1_4") (pintype "passive"))
    )
    (net (code "30") (name "ADATA3") (class "Default")
      (node (ref "IC10") (pin "8") (pinfunction "4D_8") (pintype "input"))
      (node (ref "IC10") (pin "9") (pinfunction "4Q_9") (pintype "tri_state"))
      (node (ref "IC12") (pin "8") (pinfunction "A4_8") (pintype "input"))
      (node (ref "IC15") (pin "8") (pinfunction "4D_8") (pintype "input"))
      (node (ref "IC15") (pin "9") (pinfunction "4Q_9") (pintype "tri_state"))
      (node (ref "IC17") (pin "8") (pinfunction "4D_8") (pintype "input"))
      (node (ref "IC17") (pin "9") (pinfunction "4Q_9") (pintype "tri_state"))
      (node (ref "IC21") (pin "8") (pinfunction "4D_8") (pintype "input"))
      (node (ref "IC21") (pin "9") (pinfunction "4Q_9") (pintype "tri_state"))
      (node (ref "IC23") (pin "8") (pinfunction "4D_8") (pintype "input"))
      (node (ref "IC23") (pin "9") (pinfunction "4Q_9") (pintype "tri_state"))
      (node (ref "IC26") (pin "8") (pinfunction "4D_8") (pintype "input"))
      (node (ref "IC26") (pin "9") (pinfunction "4Q_9") (pintype "tri_state"))
      (node (ref "IC28") (pin "8") (pinfunction "4D_8") (pintype "input"))
      (node (ref "IC28") (pin "9") (pinfunction "4Q_9") (pintype "tri_state"))
      (node (ref "IC30") (pin "8") (pinfunction "4D_8") (pintype "input"))
      (node (ref "IC30") (pin "9") (pinfunction "4Q_9") (pintype "tri_state"))
      (node (ref "IC7") (pin "15") (pinfunction "B4_15") (pintype "bidirectional"))
      (node (ref "RN1") (pin "5") (pinfunction "1_5") (pintype "passive"))
    )
    (net (code "31") (name "ADATA4") (class "Default")
      (node (ref "IC10") (pin "12") (pinfunction "5Q_12") (pintype "tri_state"))
      (node (ref "IC10") (pin "13") (pinfunction "5D_13") (pintype "input"))
      (node (ref "IC12") (pin "11") (pinfunction "A1_11") (pintype "input"))
      (node (ref "IC15") (pin "12") (pinfunction "5Q_12") (pintype "tri_state"))
      (node (ref "IC15") (pin "13") (pinfunction "5D_13") (pintype "input"))
      (node (ref "IC17") (pin "12") (pinfunction "5Q_12") (pintype "tri_state"))
      (node (ref "IC17") (pin "13") (pinfunction "5D_13") (pintype "input"))
      (node (ref "IC21") (pin "12") (pinfunction "5Q_12") (pintype "tri_state"))
      (node (ref "IC21") (pin "13") (pinfunction "5D_13") (pintype "input"))
      (node (ref "IC23") (pin "12") (pinfunction "5Q_12") (pintype "tri_state"))
      (node (ref "IC23") (pin "13") (pinfunction "5D_13") (pintype "input"))
      (node (ref "IC26") (pin "12") (pinfunction "5Q_12") (pintype "tri_state"))
      (node (ref "IC26") (pin "13") (pinfunction "5D_13") (pintype "input"))
      (node (ref "IC28") (pin "12") (pinfunction "5Q_12") (pintype "tri_state"))
      (node (ref "IC28") (pin "13") (pinfunction "5D_13") (pintype "input"))
      (node (ref "IC30") (pin "12") (pinfunction "5Q_12") (pintype "tri_state"))
      (node (ref "IC30") (pin "13") (pinfunction "5D_13") (pintype "input"))
      (node (ref "IC7") (pin "14") (pinfunction "B5_14") (pintype "bidirectional"))
      (node (ref "RN1") (pin "6") (pinfunction "1_6") (pintype "passive"))
    )
    (net (code "32") (name "ADATA5") (class "Default")
      (node (ref "IC10") (pin "14") (pinfunction "6D_14") (pintype "input"))
      (node (ref "IC10") (pin "15") (pinfunction "6Q_15") (pintype "tri_state"))
      (node (ref "IC12") (pin "13") (pinfunction "A2_13") (pintype "input"))
      (node (ref "IC15") (pin "14") (pinfunction "6D_14") (pintype "input"))
      (node (ref "IC15") (pin "15") (pinfunction "6Q_15") (pintype "tri_state"))
      (node (ref "IC17") (pin "14") (pinfunction "6D_14") (pintype "input"))
      (node (ref "IC17") (pin "15") (pinfunction "6Q_15") (pintype "tri_state"))
      (node (ref "IC21") (pin "14") (pinfunction "6D_14") (pintype "input"))
      (node (ref "IC21") (pin "15") (pinfunction "6Q_15") (pintype "tri_state"))
      (node (ref "IC23") (pin "14") (pinfunction "6D_14") (pintype "input"))
      (node (ref "IC23") (pin "15") (pinfunction "6Q_15") (pintype "tri_state"))
      (node (ref "IC26") (pin "14") (pinfunction "6D_14") (pintype "input"))
      (node (ref "IC26") (pin "15") (pinfunction "6Q_15") (pintype "tri_state"))
      (node (ref "IC28") (pin "14") (pinfunction "6D_14") (pintype "input"))
      (node (ref "IC28") (pin "15") (pinfunction "6Q_15") (pintype "tri_state"))
      (node (ref "IC30") (pin "14") (pinfunction "6D_14") (pintype "input"))
      (node (ref "IC30") (pin "15") (pinfunction "6Q_15") (pintype "tri_state"))
      (node (ref "IC7") (pin "13") (pinfunction "B6_13") (pintype "bidirectional"))
      (node (ref "RN1") (pin "7") (pinfunction "1_7") (pintype "passive"))
    )
    (net (code "33") (name "ADATA6") (class "Default")
      (node (ref "IC10") (pin "16") (pinfunction "7Q_16") (pintype "tri_state"))
      (node (ref "IC10") (pin "17") (pinfunction "7D_17") (pintype "input"))
      (node (ref "IC12") (pin "15") (pinfunction "A3_15") (pintype "input"))
      (node (ref "IC15") (pin "16") (pinfunction "7Q_16") (pintype "tri_state"))
      (node (ref "IC15") (pin "17") (pinfunction "7D_17") (pintype "input"))
      (node (ref "IC17") (pin "16") (pinfunction "7Q_16") (pintype "tri_state"))
      (node (ref "IC17") (pin "17") (pinfunction "7D_17") (pintype "input"))
      (node (ref "IC21") (pin "16") (pinfunction "7Q_16") (pintype "tri_state"))
      (node (ref "IC21") (pin "17") (pinfunction "7D_17") (pintype "input"))
      (node (ref "IC23") (pin "16") (pinfunction "7Q_16") (pintype "tri_state"))
      (node (ref "IC23") (pin "17") (pinfunction "7D_17") (pintype "input"))
      (node (ref "IC26") (pin "16") (pinfunction "7Q_16") (pintype "tri_state"))
      (node (ref "IC26") (pin "17") (pinfunction "7D_17") (pintype "input"))
      (node (ref "IC28") (pin "16") (pinfunction "7Q_16") (pintype "tri_state"))
      (node (ref "IC28") (pin "17") (pinfunction "7D_17") (pintype "input"))
      (node (ref "IC30") (pin "16") (pinfunction "7Q_16") (pintype "tri_state"))
      (node (ref "IC30") (pin "17") (pinfunction "7D_17") (pintype "input"))
      (node (ref "IC7") (pin "12") (pinfunction "B7_12") (pintype "bidirectional"))
      (node (ref "RN1") (pin "8") (pinfunction "1_8") (pintype "passive"))
    )
    (net (code "34") (name "ADATA7") (class "Default")
      (node (ref "IC10") (pin "18") (pinfunction "8D_18") (pintype "input"))
      (node (ref "IC10") (pin "19") (pinfunction "8Q_19") (pintype "tri_state"))
      (node (ref "IC12") (pin "17") (pinfunction "A4_17") (pintype "input"))
      (node (ref "IC15") (pin "18") (pinfunction "8D_18") (pintype "input"))
      (node (ref "IC15") (pin "19") (pinfunction "8Q_19") (pintype "tri_state"))
      (node (ref "IC17") (pin "18") (pinfunction "8D_18") (pintype "input"))
      (node (ref "IC17") (pin "19") (pinfunction "8Q_19") (pintype "tri_state"))
      (node (ref "IC21") (pin "18") (pinfunction "8D_18") (pintype "input"))
      (node (ref "IC21") (pin "19") (pinfunction "8Q_19") (pintype "tri_state"))
      (node (ref "IC23") (pin "18") (pinfunction "8D_18") (pintype "input"))
      (node (ref "IC23") (pin "19") (pinfunction "8Q_19") (pintype "tri_state"))
      (node (ref "IC26") (pin "18") (pinfunction "8D_18") (pintype "input"))
      (node (ref "IC26") (pin "19") (pinfunction "8Q_19") (pintype "tri_state"))
      (node (ref "IC28") (pin "18") (pinfunction "8D_18") (pintype "input"))
      (node (ref "IC28") (pin "19") (pinfunction "8Q_19") (pintype "tri_state"))
      (node (ref "IC30") (pin "18") (pinfunction "8D_18") (pintype "input"))
      (node (ref "IC30") (pin "19") (pinfunction "8Q_19") (pintype "tri_state"))
      (node (ref "IC7") (pin "11") (pinfunction "B8_11") (pintype "bidirectional"))
      (node (ref "RN1") (pin "9") (pinfunction "1_9") (pintype "passive"))
    )
    (net (code "35") (name "ADATA8") (class "Default")
      (node (ref "IC11") (pin "2") (pinfunction "A1_2") (pintype "input"))
      (node (ref "IC16") (pin "2") (pinfunction "1Q_2") (pintype "tri_state"))
      (node (ref "IC16") (pin "3") (pinfunction "1D_3") (pintype "input"))
      (node (ref "IC18") (pin "2") (pinfunction "1Q_2") (pintype "tri_state"))
      (node (ref "IC18") (pin "3") (pinfunction "1D_3") (pintype "input"))
      (node (ref "IC22") (pin "2") (pinfunction "1Q_2") (pintype "tri_state"))
      (node (ref "IC22") (pin "3") (pinfunction "1D_3") (pintype "input"))
      (node (ref "IC24") (pin "2") (pinfunction "1Q_2") (pintype "tri_state"))
      (node (ref "IC24") (pin "3") (pinfunction "1D_3") (pintype "input"))
      (node (ref "IC25") (pin "2") (pinfunction "1Q_2") (pintype "tri_state"))
      (node (ref "IC25") (pin "3") (pinfunction "1D_3") (pintype "input"))
      (node (ref "IC27") (pin "2") (pinfunction "1Q_2") (pintype "tri_state"))
      (node (ref "IC27") (pin "3") (pinfunction "1D_3") (pintype "input"))
      (node (ref "IC29") (pin "2") (pinfunction "1Q_2") (pintype "tri_state"))
      (node (ref "IC29") (pin "3") (pinfunction "1D_3") (pintype "input"))
      (node (ref "IC31") (pin "2") (pinfunction "1Q_2") (pintype "tri_state"))
      (node (ref "IC31") (pin "3") (pinfunction "1D_3") (pintype "input"))
      (node (ref "IC8") (pin "18") (pinfunction "B1_18") (pintype "bidirectional"))
      (node (ref "IC9") (pin "18") (pinfunction "B1_18") (pintype "bidirectional"))
      (node (ref "RN2") (pin "2") (pinfunction "1_2") (pintype "passive"))
    )
    (net (code "36") (name "ADATA9") (class "Default")
      (node (ref "IC11") (pin "4") (pinfunction "A2_4") (pintype "input"))
      (node (ref "IC16") (pin "4") (pinfunction "2D_4") (pintype "input"))
      (node (ref "IC16") (pin "5") (pinfunction "2Q_5") (pintype "tri_state"))
      (node (ref "IC18") (pin "4") (pinfunction "2D_4") (pintype "input"))
      (node (ref "IC18") (pin "5") (pinfunction "2Q_5") (pintype "tri_state"))
      (node (ref "IC22") (pin "4") (pinfunction "2D_4") (pintype "input"))
      (node (ref "IC22") (pin "5") (pinfunction "2Q_5") (pintype "tri_state"))
      (node (ref "IC24") (pin "4") (pinfunction "2D_4") (pintype "input"))
      (node (ref "IC24") (pin "5") (pinfunction "2Q_5") (pintype "tri_state"))
      (node (ref "IC25") (pin "4") (pinfunction "2D_4") (pintype "input"))
      (node (ref "IC25") (pin "5") (pinfunction "2Q_5") (pintype "tri_state"))
      (node (ref "IC27") (pin "4") (pinfunction "2D_4") (pintype "input"))
      (node (ref "IC27") (pin "5") (pinfunction "2Q_5") (pintype "tri_state"))
      (node (ref "IC29") (pin "4") (pinfunction "2D_4") (pintype "input"))
      (node (ref "IC29") (pin "5") (pinfunction "2Q_5") (pintype "tri_state"))
      (node (ref "IC31") (pin "4") (pinfunction "2D_4") (pintype "input"))
      (node (ref "IC31") (pin "5") (pinfunction "2Q_5") (pintype "tri_state"))
      (node (ref "IC8") (pin "17") (pinfunction "B2_17") (pintype "bidirectional"))
      (node (ref "IC9") (pin "17") (pinfunction "B2_17") (pintype "bidirectional"))
      (node (ref "RN2") (pin "3") (pinfunction "1_3") (pintype "passive"))
    )
    (net (code "37") (name "ADATA10") (class "Default")
      (node (ref "IC11") (pin "6") (pinfunction "A3_6") (pintype "input"))
      (node (ref "IC16") (pin "6") (pinfunction "3Q_6") (pintype "tri_state"))
      (node (ref "IC16") (pin "7") (pinfunction "3D_7") (pintype "input"))
      (node (ref "IC18") (pin "6") (pinfunction "3Q_6") (pintype "tri_state"))
      (node (ref "IC18") (pin "7") (pinfunction "3D_7") (pintype "input"))
      (node (ref "IC22") (pin "6") (pinfunction "3Q_6") (pintype "tri_state"))
      (node (ref "IC22") (pin "7") (pinfunction "3D_7") (pintype "input"))
      (node (ref "IC24") (pin "6") (pinfunction "3Q_6") (pintype "tri_state"))
      (node (ref "IC24") (pin "7") (pinfunction "3D_7") (pintype "input"))
      (node (ref "IC25") (pin "6") (pinfunction "3Q_6") (pintype "tri_state"))
      (node (ref "IC25") (pin "7") (pinfunction "3D_7") (pintype "input"))
      (node (ref "IC27") (pin "6") (pinfunction "3Q_6") (pintype "tri_state"))
      (node (ref "IC27") (pin "7") (pinfunction "3D_7") (pintype "input"))
      (node (ref "IC29") (pin "6") (pinfunction "3Q_6") (pintype "tri_state"))
      (node (ref "IC29") (pin "7") (pinfunction "3D_7") (pintype "input"))
      (node (ref "IC31") (pin "6") (pinfunction "3Q_6") (pintype "tri_state"))
      (node (ref "IC31") (pin "7") (pinfunction "3D_7") (pintype "input"))
      (node (ref "IC8") (pin "16") (pinfunction "B3_16") (pintype "bidirectional"))
      (node (ref "IC9") (pin "16") (pinfunction "B3_16") (pintype "bidirectional"))
      (node (ref "RN2") (pin "4") (pinfunction "1_4") (pintype "passive"))
    )
    (net (code "38") (name "ADATA11") (class "Default")
      (node (ref "IC11") (pin "8") (pinfunction "A4_8") (pintype "input"))
      (node (ref "IC16") (pin "8") (pinfunction "4D_8") (pintype "input"))
      (node (ref "IC16") (pin "9") (pinfunction "4Q_9") (pintype "tri_state"))
      (node (ref "IC18") (pin "8") (pinfunction "4D_8") (pintype "input"))
      (node (ref "IC18") (pin "9") (pinfunction "4Q_9") (pintype "tri_state"))
      (node (ref "IC22") (pin "8") (pinfunction "4D_8") (pintype "input"))
      (node (ref "IC22") (pin "9") (pinfunction "4Q_9") (pintype "tri_state"))
      (node (ref "IC24") (pin "8") (pinfunction "4D_8") (pintype "input"))
      (node (ref "IC24") (pin "9") (pinfunction "4Q_9") (pintype "tri_state"))
      (node (ref "IC25") (pin "8") (pinfunction "4D_8") (pintype "input"))
      (node (ref "IC25") (pin "9") (pinfunction "4Q_9") (pintype "tri_state"))
      (node (ref "IC27") (pin "8") (pinfunction "4D_8") (pintype "input"))
      (node (ref "IC27") (pin "9") (pinfunction "4Q_9") (pintype "tri_state"))
      (node (ref "IC29") (pin "8") (pinfunction "4D_8") (pintype "input"))
      (node (ref "IC29") (pin "9") (pinfunction "4Q_9") (pintype "tri_state"))
      (node (ref "IC31") (pin "8") (pinfunction "4D_8") (pintype "input"))
      (node (ref "IC31") (pin "9") (pinfunction "4Q_9") (pintype "tri_state"))
      (node (ref "IC8") (pin "15") (pinfunction "B4_15") (pintype "bidirectional"))
      (node (ref "IC9") (pin "15") (pinfunction "B4_15") (pintype "bidirectional"))
      (node (ref "RN2") (pin "5") (pinfunction "1_5") (pintype "passive"))
    )
    (net (code "39") (name "ADATA12") (class "Default")
      (node (ref "IC11") (pin "11") (pinfunction "A1_11") (pintype "input"))
      (node (ref "IC16") (pin "12") (pinfunction "5Q_12") (pintype "tri_state"))
      (node (ref "IC16") (pin "13") (pinfunction "5D_13") (pintype "input"))
      (node (ref "IC18") (pin "12") (pinfunction "5Q_12") (pintype "tri_state"))
      (node (ref "IC18") (pin "13") (pinfunction "5D_13") (pintype "input"))
      (node (ref "IC22") (pin "12") (pinfunction "5Q_12") (pintype "tri_state"))
      (node (ref "IC22") (pin "13") (pinfunction "5D_13") (pintype "input"))
      (node (ref "IC24") (pin "12") (pinfunction "5Q_12") (pintype "tri_state"))
      (node (ref "IC24") (pin "13") (pinfunction "5D_13") (pintype "input"))
      (node (ref "IC25") (pin "12") (pinfunction "5Q_12") (pintype "tri_state"))
      (node (ref "IC25") (pin "13") (pinfunction "5D_13") (pintype "input"))
      (node (ref "IC27") (pin "12") (pinfunction "5Q_12") (pintype "tri_state"))
      (node (ref "IC27") (pin "13") (pinfunction "5D_13") (pintype "input"))
      (node (ref "IC29") (pin "12") (pinfunction "5Q_12") (pintype "tri_state"))
      (node (ref "IC29") (pin "13") (pinfunction "5D_13") (pintype "input"))
      (node (ref "IC31") (pin "12") (pinfunction "5Q_12") (pintype "tri_state"))
      (node (ref "IC31") (pin "13") (pinfunction "5D_13") (pintype "input"))
      (node (ref "IC8") (pin "14") (pinfunction "B5_14") (pintype "bidirectional"))
      (node (ref "IC9") (pin "14") (pinfunction "B5_14") (pintype "bidirectional"))
      (node (ref "RN2") (pin "6") (pinfunction "1_6") (pintype "passive"))
    )
    (net (code "40") (name "ADATA13") (class "Default")
      (node (ref "IC11") (pin "13") (pinfunction "A2_13") (pintype "input"))
      (node (ref "IC16") (pin "14") (pinfunction "6D_14") (pintype "input"))
      (node (ref "IC16") (pin "15") (pinfunction "6Q_15") (pintype "tri_state"))
      (node (ref "IC18") (pin "14") (pinfunction "6D_14") (pintype "input"))
      (node (ref "IC18") (pin "15") (pinfunction "6Q_15") (pintype "tri_state"))
      (node (ref "IC22") (pin "14") (pinfunction "6D_14") (pintype "input"))
      (node (ref "IC22") (pin "15") (pinfunction "6Q_15") (pintype "tri_state"))
      (node (ref "IC24") (pin "14") (pinfunction "6D_14") (pintype "input"))
      (node (ref "IC24") (pin "15") (pinfunction "6Q_15") (pintype "tri_state"))
      (node (ref "IC25") (pin "14") (pinfunction "6D_14") (pintype "input"))
      (node (ref "IC25") (pin "15") (pinfunction "6Q_15") (pintype "tri_state"))
      (node (ref "IC27") (pin "14") (pinfunction "6D_14") (pintype "input"))
      (node (ref "IC27") (pin "15") (pinfunction "6Q_15") (pintype "tri_state"))
      (node (ref "IC29") (pin "14") (pinfunction "6D_14") (pintype "input"))
      (node (ref "IC29") (pin "15") (pinfunction "6Q_15") (pintype "tri_state"))
      (node (ref "IC31") (pin "14") (pinfunction "6D_14") (pintype "input"))
      (node (ref "IC31") (pin "15") (pinfunction "6Q_15") (pintype "tri_state"))
      (node (ref "IC8") (pin "13") (pinfunction "B6_13") (pintype "bidirectional"))
      (node (ref "IC9") (pin "13") (pinfunction "B6_13") (pintype "bidirectional"))
      (node (ref "RN2") (pin "7") (pinfunction "1_7") (pintype "passive"))
    )
    (net (code "41") (name "ADATA14") (class "Default")
      (node (ref "IC11") (pin "15") (pinfunction "A3_15") (pintype "input"))
      (node (ref "IC16") (pin "16") (pinfunction "7Q_16") (pintype "tri_state"))
      (node (ref "IC16") (pin "17") (pinfunction "7D_17") (pintype "input"))
      (node (ref "IC18") (pin "16") (pinfunction "7Q_16") (pintype "tri_state"))
      (node (ref "IC18") (pin "17") (pinfunction "7D_17") (pintype "input"))
      (node (ref "IC22") (pin "16") (pinfunction "7Q_16") (pintype "tri_state"))
      (node (ref "IC22") (pin "17") (pinfunction "7D_17") (pintype "input"))
      (node (ref "IC24") (pin "16") (pinfunction "7Q_16") (pintype "tri_state"))
      (node (ref "IC24") (pin "17") (pinfunction "7D_17") (pintype "input"))
      (node (ref "IC25") (pin "16") (pinfunction "7Q_16") (pintype "tri_state"))
      (node (ref "IC25") (pin "17") (pinfunction "7D_17") (pintype "input"))
      (node (ref "IC27") (pin "16") (pinfunction "7Q_16") (pintype "tri_state"))
      (node (ref "IC27") (pin "17") (pinfunction "7D_17") (pintype "input"))
      (node (ref "IC29") (pin "16") (pinfunction "7Q_16") (pintype "tri_state"))
      (node (ref "IC29") (pin "17") (pinfunction "7D_17") (pintype "input"))
      (node (ref "IC31") (pin "16") (pinfunction "7Q_16") (pintype "tri_state"))
      (node (ref "IC31") (pin "17") (pinfunction "7D_17") (pintype "input"))
      (node (ref "IC8") (pin "12") (pinfunction "B7_12") (pintype "bidirectional"))
      (node (ref "IC9") (pin "12") (pinfunction "B7_12") (pintype "bidirectional"))
      (node (ref "RN2") (pin "8") (pinfunction "1_8") (pintype "passive"))
    )
    (net (code "42") (name "ADATA15") (class "Default")
      (node (ref "IC11") (pin "17") (pinfunction "A4_17") (pintype "input"))
      (node (ref "IC16") (pin "18") (pinfunction "8D_18") (pintype "input"))
      (node (ref "IC16") (pin "19") (pinfunction "8Q_19") (pintype "tri_state"))
      (node (ref "IC18") (pin "18") (pinfunction "8D_18") (pintype "input"))
      (node (ref "IC18") (pin "19") (pinfunction "8Q_19") (pintype "tri_state"))
      (node (ref "IC22") (pin "18") (pinfunction "8D_18") (pintype "input"))
      (node (ref "IC22") (pin "19") (pinfunction "8Q_19") (pintype "tri_state"))
      (node (ref "IC24") (pin "18") (pinfunction "8D_18") (pintype "input"))
      (node (ref "IC24") (pin "19") (pinfunction "8Q_19") (pintype "tri_state"))
      (node (ref "IC25") (pin "18") (pinfunction "8D_18") (pintype "input"))
      (node (ref "IC25") (pin "19") (pinfunction "8Q_19") (pintype "tri_state"))
      (node (ref "IC27") (pin "18") (pinfunction "8D_18") (pintype "input"))
      (node (ref "IC27") (pin "19") (pinfunction "8Q_19") (pintype "tri_state"))
      (node (ref "IC29") (pin "18") (pinfunction "8D_18") (pintype "input"))
      (node (ref "IC29") (pin "19") (pinfunction "8Q_19") (pintype "tri_state"))
      (node (ref "IC31") (pin "18") (pinfunction "8D_18") (pintype "input"))
      (node (ref "IC31") (pin "19") (pinfunction "8Q_19") (pintype "tri_state"))
      (node (ref "IC8") (pin "11") (pinfunction "B8_11") (pintype "bidirectional"))
      (node (ref "IC9") (pin "11") (pinfunction "B8_11") (pintype "bidirectional"))
      (node (ref "RN2") (pin "9") (pinfunction "1_9") (pintype "passive"))
    )
    (net (code "43") (name "ADDR-ID0") (class "Default")
      (node (ref "X1") (pin "B9") (pinfunction "B_B9") (pintype "passive"))
    )
    (net (code "44") (name "ADDR-ID1") (class "Default")
      (node (ref "X1") (pin "B10") (pinfunction "B_B10") (pintype "passive"))
    )
    (net (code "45") (name "ADDR-REG-ADDR-RD") (class "Default")
      (node (ref "X1") (pin "C10") (pinfunction "B_C10") (pintype "passive"))
    )
    (net (code "46") (name "ADDR-REG-DATA-RD-HI") (class "Default")
      (node (ref "X1") (pin "C9") (pinfunction "B_C9") (pintype "passive"))
    )
    (net (code "47") (name "ADDR-REG-DATA-RD-LO") (class "Default")
      (node (ref "X1") (pin "C8") (pinfunction "B_C8") (pintype "passive"))
    )
    (net (code "48") (name "ADDR-REG-DN") (class "Default")
      (node (ref "X1") (pin "C13") (pinfunction "B_C13") (pintype "passive"))
    )
    (net (code "49") (name "ADDR-REG-FUNC-LD") (class "Default")
      (node (ref "X1") (pin "C6") (pinfunction "B_C6") (pintype "passive"))
    )
    (net (code "50") (name "ADDR-REG-FUNC-RD") (class "Default")
      (node (ref "X1") (pin "C7") (pinfunction "B_C7") (pintype "passive"))
    )
    (net (code "51") (name "ADDR-REG-LD-HI") (class "Default")
      (node (ref "X1") (pin "C12") (pinfunction "B_C12") (pintype "passive"))
    )
    (net (code "52") (name "ADDR-REG-LD-LO") (class "Default")
      (node (ref "X1") (pin "C11") (pinfunction "B_C11") (pintype "passive"))
    )
    (net (code "53") (name "ADDR-REG-UP") (class "Default")
      (node (ref "X1") (pin "C14") (pinfunction "B_C14") (pintype "passive"))
    )
    (net (code "54") (name "ADDR0") (class "Default")
      (node (ref "X1") (pin "A3") (pinfunction "B_A3") (pintype "passive"))
    )
    (net (code "55") (name "ADDR1") (class "Default")
      (node (ref "X1") (pin "A4") (pinfunction "B_A4") (pintype "passive"))
    )
    (net (code "56") (name "ADDR2") (class "Default")
      (node (ref "X1") (pin "A5") (pinfunction "B_A5") (pintype "passive"))
    )
    (net (code "57") (name "ADDR3") (class "Default")
      (node (ref "X1") (pin "A6") (pinfunction "B_A6") (pintype "passive"))
    )
    (net (code "58") (name "ADDR4") (class "Default")
      (node (ref "X1") (pin "A7") (pinfunction "B_A7") (pintype "passive"))
    )
    (net (code "59") (name "ADDR5") (class "Default")
      (node (ref "X1") (pin "A8") (pinfunction "B_A8") (pintype "passive"))
    )
    (net (code "60") (name "ADDR6") (class "Default")
      (node (ref "X1") (pin "A9") (pinfunction "B_A9") (pintype "passive"))
    )
    (net (code "61") (name "ADDR7") (class "Default")
      (node (ref "X1") (pin "A10") (pinfunction "B_A10") (pintype "passive"))
    )
    (net (code "62") (name "ADDR8") (class "Default")
      (node (ref "X1") (pin "A11") (pinfunction "B_A11") (pintype "passive"))
    )
    (net (code "63") (name "ADDR9") (class "Default")
      (node (ref "X1") (pin "A12") (pinfunction "B_A12") (pintype "passive"))
    )
    (net (code "64") (name "ADDR10") (class "Default")
      (node (ref "X1") (pin "A13") (pinfunction "B_A13") (pintype "passive"))
    )
    (net (code "65") (name "ADDR11") (class "Default")
      (node (ref "X1") (pin "A14") (pinfunction "B_A14") (pintype "passive"))
    )
    (net (code "66") (name "ADDR12") (class "Default")
      (node (ref "X1") (pin "A15") (pinfunction "B_A15") (pintype "passive"))
    )
    (net (code "67") (name "ADDR13") (class "Default")
      (node (ref "X1") (pin "A16") (pinfunction "B_A16") (pintype "passive"))
    )
    (net (code "68") (name "ADDR14") (class "Default")
      (node (ref "X1") (pin "A17") (pinfunction "B_A17") (pintype "passive"))
    )
    (net (code "69") (name "ADDR15") (class "Default")
      (node (ref "X1") (pin "A18") (pinfunction "B_A18") (pintype "passive"))
    )
    (net (code "70") (name "ALU-FUNC") (class "Default")
      (node (ref "X1") (pin "C15") (pinfunction "B_C15") (pintype "passive"))
    )
    (net (code "71") (name "ALU0") (class "Default")
      (node (ref "X1") (pin "C16") (pinfunction "B_C16") (pintype "passive"))
    )
    (net (code "72") (name "ALU1") (class "Default")
      (node (ref "X1") (pin "C17") (pinfunction "B_C17") (pintype "passive"))
    )
    (net (code "73") (name "ALU2") (class "Default")
      (node (ref "X1") (pin "C18") (pinfunction "B_C18") (pintype "passive"))
    )
    (net (code "74") (name "ALU3") (class "Default")
      (node (ref "X1") (pin "C19") (pinfunction "B_C19") (pintype "passive"))
    )
    (net (code "75") (name "BR-COND") (class "Default")
      (node (ref "X1") (pin "C24") (pinfunction "B_C24") (pintype "passive"))
    )
    (net (code "76") (name "BUS-DIR") (class "Default")
      (node (ref "IC1") (pin "10") (pinfunction "O_10") (pintype "output"))
      (node (ref "IC7") (pin "1") (pinfunction "DIR_1") (pintype "input"))
      (node (ref "IC8") (pin "1") (pinfunction "DIR_1") (pintype "input"))
      (node (ref "IC9") (pin "1") (pinfunction "DIR_1") (pintype "input"))
    )
    (net (code "77") (name "CLK0H") (class "Default")
      (node (ref "IC14") (pin "4") (pinfunction "O_4") (pintype "output"))
      (node (ref "IC16") (pin "11") (pinfunction "CLK_11") (pintype "input"))
      (node (ref "IC34") (pin "15") (pinfunction "A3_15") (pintype "input"))
    )
    (net (code "78") (name "CLK0L") (class "Default")
      (node (ref "IC14") (pin "1") (pinfunction "O_1") (pintype "output"))
      (node (ref "IC15") (pin "11") (pinfunction "CLK_11") (pintype "input"))
      (node (ref "IC34") (pin "17") (pinfunction "A4_17") (pintype "input"))
    )
    (net (code "79") (name "CLK1H") (class "Default")
      (node (ref "IC14") (pin "13") (pinfunction "O_13") (pintype "output"))
      (node (ref "IC18") (pin "11") (pinfunction "CLK_11") (pintype "input"))
      (node (ref "IC34") (pin "11") (pinfunction "A1_11") (pintype "input"))
    )
    (net (code "80") (name "CLK1L") (class "Default")
      (node (ref "IC14") (pin "10") (pinfunction "O_10") (pintype "output"))
      (node (ref "IC17") (pin "11") (pinfunction "CLK_11") (pintype "input"))
      (node (ref "IC34") (pin "13") (pinfunction "A2_13") (pintype "input"))
    )
    (net (code "81") (name "CLK2H") (class "Default")
      (node (ref "IC20") (pin "4") (pinfunction "O_4") (pintype "output"))
      (node (ref "IC22") (pin "11") (pinfunction "CLK_11") (pintype "input"))
      (node (ref "IC33") (pin "4") (pinfunction "A2_4") (pintype "input"))
    )
    (net (code "82") (name "CLK2L") (class "Default")
      (node (ref "IC20") (pin "1") (pinfunction "O_1") (pintype "output"))
      (node (ref "IC21") (pin "11") (pinfunction "CLK_11") (pintype "input"))
      (node (ref "IC33") (pin "2") (pinfunction "A1_2") (pintype "input"))
    )
    (net (code "83") (name "CLK3H") (class "Default")
      (node (ref "IC20") (pin "13") (pinfunction "O_13") (pintype "output"))
      (node (ref "IC24") (pin "11") (pinfunction "CLK_11") (pintype "input"))
      (node (ref "IC33") (pin "8") (pinfunction "A4_8") (pintype "input"))
    )
    (net (code "84") (name "CLK3L") (class "Default")
      (node (ref "IC20") (pin "10") (pinfunction "O_10") (pintype "output"))
      (node (ref "IC23") (pin "11") (pinfunction "CLK_11") (pintype "input"))
      (node (ref "IC33") (pin "6") (pinfunction "A3_6") (pintype "input"))
    )
    (net (code "85") (name "CLK4H") (class "Default")
      (node (ref "IC25") (pin "11") (pinfunction "CLK_11") (pintype "input"))
      (node (ref "IC34") (pin "6") (pinfunction "A3_6") (pintype "input"))
      (node (ref "IC35") (pin "4") (pinfunction "O_4") (pintype "output"))
    )
    (net (code "86") (name "CLK4L") (class "Default")
      (node (ref "IC10") (pin "11") (pinfunction "CLK_11") (pintype "input"))
      (node (ref "IC34") (pin "8") (pinfunction "A4_8") (pintype "input"))
      (node (ref "IC35") (pin "1") (pinfunction "O_1") (pintype "output"))
    )
    (net (code "87") (name "CLK5H") (class "Default")
      (node (ref "IC29") (pin "11") (pinfunction "CLK_11") (pintype "input"))
      (node (ref "IC34") (pin "2") (pinfunction "A1_2") (pintype "input"))
      (node (ref "IC35") (pin "13") (pinfunction "O_13") (pintype "output"))
    )
    (net (code "88") (name "CLK5L") (class "Default")
      (node (ref "IC28") (pin "11") (pinfunction "CLK_11") (pintype "input"))
      (node (ref "IC34") (pin "4") (pinfunction "A2_4") (pintype "input"))
      (node (ref "IC35") (pin "10") (pinfunction "O_10") (pintype "output"))
    )
    (net (code "89") (name "CLK6H") (class "Default")
      (node (ref "IC27") (pin "11") (pinfunction "CLK_11") (pintype "input"))
      (node (ref "IC33") (pin "13") (pinfunction "A2_13") (pintype "input"))
      (node (ref "IC38") (pin "4") (pinfunction "O_4") (pintype "output"))
    )
    (net (code "90") (name "CLK6L") (class "Default")
      (node (ref "IC26") (pin "11") (pinfunction "CLK_11") (pintype "input"))
      (node (ref "IC33") (pin "11") (pinfunction "A1_11") (pintype "input"))
      (node (ref "IC38") (pin "1") (pinfunction "O_1") (pintype "output"))
    )
    (net (code "91") (name "CLK7H") (class "Default")
      (node (ref "IC31") (pin "11") (pinfunction "CLK_11") (pintype "input"))
      (node (ref "IC33") (pin "17") (pinfunction "A4_17") (pintype "input"))
      (node (ref "IC38") (pin "13") (pinfunction "O_13") (pintype "output"))
    )
    (net (code "92") (name "CLK7L") (class "Default")
      (node (ref "IC30") (pin "11") (pinfunction "CLK_11") (pintype "input"))
      (node (ref "IC33") (pin "15") (pinfunction "A3_15") (pintype "input"))
      (node (ref "IC38") (pin "10") (pinfunction "O_10") (pintype "output"))
    )
    (net (code "93") (name "DATA0") (class "Default")
      (node (ref "IC7") (pin "2") (pinfunction "A1_2") (pintype "bidirectional"))
      (node (ref "IC9") (pin "2") (pinfunction "A1_2") (pintype "bidirectional"))
      (node (ref "X1") (pin "A19") (pinfunction "B_A19") (pintype "passive"))
    )
    (net (code "94") (name "DATA1") (class "Default")
      (node (ref "IC7") (pin "3") (pinfunction "A2_3") (pintype "bidirectional"))
      (node (ref "IC9") (pin "3") (pinfunction "A2_3") (pintype "bidirectional"))
      (node (ref "X1") (pin "A20") (pinfunction "B_A20") (pintype "passive"))
    )
    (net (code "95") (name "DATA2") (class "Default")
      (node (ref "IC7") (pin "4") (pinfunction "A3_4") (pintype "bidirectional"))
      (node (ref "IC9") (pin "4") (pinfunction "A3_4") (pintype "bidirectional"))
      (node (ref "X1") (pin "A21") (pinfunction "B_A21") (pintype "passive"))
    )
    (net (code "96") (name "DATA3") (class "Default")
      (node (ref "IC7") (pin "5") (pinfunction "A4_5") (pintype "bidirectional"))
      (node (ref "IC9") (pin "5") (pinfunction "A4_5") (pintype "bidirectional"))
      (node (ref "X1") (pin "A22") (pinfunction "B_A22") (pintype "passive"))
    )
    (net (code "97") (name "DATA4") (class "Default")
      (node (ref "IC7") (pin "6") (pinfunction "A5_6") (pintype "bidirectional"))
      (node (ref "IC9") (pin "6") (pinfunction "A5_6") (pintype "bidirectional"))
      (node (ref "X1") (pin "A23") (pinfunction "B_A23") (pintype "passive"))
    )
    (net (code "98") (name "DATA5") (class "Default")
      (node (ref "IC7") (pin "7") (pinfunction "A6_7") (pintype "bidirectional"))
      (node (ref "IC9") (pin "7") (pinfunction "A6_7") (pintype "bidirectional"))
      (node (ref "X1") (pin "A24") (pinfunction "B_A24") (pintype "passive"))
    )
    (net (code "99") (name "DATA6") (class "Default")
      (node (ref "IC7") (pin "8") (pinfunction "A7_8") (pintype "bidirectional"))
      (node (ref "IC9") (pin "8") (pinfunction "A7_8") (pintype "bidirectional"))
      (node (ref "X1") (pin "A25") (pinfunction "B_A25") (pintype "passive"))
    )
    (net (code "100") (name "DATA7") (class "Default")
      (node (ref "IC7") (pin "9") (pinfunction "A8_9") (pintype "bidirectional"))
      (node (ref "IC9") (pin "9") (pinfunction "A8_9") (pintype "bidirectional"))
      (node (ref "X1") (pin "A26") (pinfunction "B_A26") (pintype "passive"))
    )
    (net (code "101") (name "DATA8") (class "Default")
      (node (ref "IC8") (pin "2") (pinfunction "A1_2") (pintype "bidirectional"))
      (node (ref "X1") (pin "A27") (pinfunction "B_A27") (pintype "passive"))
    )
    (net (code "102") (name "DATA9") (class "Default")
      (node (ref "IC8") (pin "3") (pinfunction "A2_3") (pintype "bidirectional"))
      (node (ref "X1") (pin "A28") (pinfunction "B_A28") (pintype "passive"))
    )
    (net (code "103") (name "DATA10") (class "Default")
      (node (ref "IC8") (pin "4") (pinfunction "A3_4") (pintype "bidirectional"))
      (node (ref "X1") (pin "A29") (pinfunction "B_A29") (pintype "passive"))
    )
    (net (code "104") (name "DATA11") (class "Default")
      (node (ref "IC8") (pin "5") (pinfunction "A4_5") (pintype "bidirectional"))
      (node (ref "X1") (pin "A30") (pinfunction "B_A30") (pintype "passive"))
    )
    (net (code "105") (name "DATA12") (class "Default")
      (node (ref "IC8") (pin "6") (pinfunction "A5_6") (pintype "bidirectional"))
      (node (ref "X1") (pin "B3") (pinfunction "B_B3") (pintype "passive"))
    )
    (net (code "106") (name "DATA13") (class "Default")
      (node (ref "IC8") (pin "7") (pinfunction "A6_7") (pintype "bidirectional"))
      (node (ref "X1") (pin "B4") (pinfunction "B_B4") (pintype "passive"))
    )
    (net (code "107") (name "DATA14") (class "Default")
      (node (ref "IC8") (pin "8") (pinfunction "A7_8") (pintype "bidirectional"))
      (node (ref "X1") (pin "B5") (pinfunction "B_B5") (pintype "passive"))
    )
    (net (code "108") (name "DATA15") (class "Default")
      (node (ref "IC8") (pin "9") (pinfunction "A8_9") (pintype "bidirectional"))
      (node (ref "X1") (pin "B6") (pinfunction "B_B6") (pintype "passive"))
    )
    (net (code "109") (name "FP-ADATA0") (class "Default")
      (node (ref "IC12") (pin "18") (pinfunction "Y1_18") (pintype "tri_state"))
      (node (ref "JP6") (pin "3") (pinfunction "3_3") (pintype "passive"))
    )
    (net (code "110") (name "FP-ADATA1") (class "Default")
      (node (ref "IC12") (pin "16") (pinfunction "Y2_16") (pintype "tri_state"))
      (node (ref "JP6") (pin "5") (pinfunction "5_5") (pintype "passive"))
    )
    (net (code "111") (name "FP-ADATA2") (class "Default")
      (node (ref "IC12") (pin "14") (pinfunction "Y3_14") (pintype "tri_state"))
      (node (ref "JP6") (pin "7") (pinfunction "7_7") (pintype "passive"))
    )
    (net (code "112") (name "FP-ADATA3") (class "Default")
      (node (ref "IC12") (pin "12") (pinfunction "Y4_12") (pintype "tri_state"))
      (node (ref "JP6") (pin "9") (pinfunction "9_9") (pintype "passive"))
    )
    (net (code "113") (name "FP-ADATA4") (class "Default")
      (node (ref "IC12") (pin "9") (pinfunction "Y1_9") (pintype "tri_state"))
      (node (ref "JP6") (pin "11") (pinfunction "11_11") (pintype "passive"))
    )
    (net (code "114") (name "FP-ADATA5") (class "Default")
      (node (ref "IC12") (pin "7") (pinfunction "Y2_7") (pintype "tri_state"))
      (node (ref "JP6") (pin "13") (pinfunction "13_13") (pintype "passive"))
    )
    (net (code "115") (name "FP-ADATA6") (class "Default")
      (node (ref "IC12") (pin "5") (pinfunction "Y3_5") (pintype "tri_state"))
      (node (ref "JP6") (pin "15") (pinfunction "15_15") (pintype "passive"))
    )
    (net (code "116") (name "FP-ADATA7") (class "Default")
      (node (ref "IC12") (pin "3") (pinfunction "Y4_3") (pintype "tri_state"))
      (node (ref "JP6") (pin "17") (pinfunction "17_17") (pintype "passive"))
    )
    (net (code "117") (name "FP-ADATA8") (class "Default")
      (node (ref "IC11") (pin "18") (pinfunction "Y1_18") (pintype "tri_state"))
      (node (ref "JP6") (pin "4") (pinfunction "4_4") (pintype "passive"))
    )
    (net (code "118") (name "FP-ADATA9") (class "Default")
      (node (ref "IC11") (pin "16") (pinfunction "Y2_16") (pintype "tri_state"))
      (node (ref "JP6") (pin "6") (pinfunction "6_6") (pintype "passive"))
    )
    (net (code "119") (name "FP-ADATA10") (class "Default")
      (node (ref "IC11") (pin "14") (pinfunction "Y3_14") (pintype "tri_state"))
      (node (ref "JP6") (pin "8") (pinfunction "8_8") (pintype "passive"))
    )
    (net (code "120") (name "FP-ADATA11") (class "Default")
      (node (ref "IC11") (pin "12") (pinfunction "Y4_12") (pintype "tri_state"))
      (node (ref "JP6") (pin "10") (pinfunction "10_10") (pintype "passive"))
    )
    (net (code "121") (name "FP-ADATA12") (class "Default")
      (node (ref "IC11") (pin "9") (pinfunction "Y1_9") (pintype "tri_state"))
      (node (ref "JP6") (pin "12") (pinfunction "12_12") (pintype "passive"))
    )
    (net (code "122") (name "FP-ADATA13") (class "Default")
      (node (ref "IC11") (pin "7") (pinfunction "Y2_7") (pintype "tri_state"))
      (node (ref "JP6") (pin "14") (pinfunction "14_14") (pintype "passive"))
    )
    (net (code "123") (name "FP-ADATA14") (class "Default")
      (node (ref "IC11") (pin "5") (pinfunction "Y3_5") (pintype "tri_state"))
      (node (ref "JP6") (pin "16") (pinfunction "16_16") (pintype "passive"))
    )
    (net (code "124") (name "FP-ADATA15") (class "Default")
      (node (ref "IC11") (pin "3") (pinfunction "Y4_3") (pintype "tri_state"))
      (node (ref "JP6") (pin "18") (pinfunction "18_18") (pintype "passive"))
    )
    (net (code "125") (name "FP-CLK0H") (class "Default")
      (node (ref "IC34") (pin "5") (pinfunction "Y3_5") (pintype "tri_state"))
      (node (ref "JP6") (pin "23") (pinfunction "23_23") (pintype "passive"))
    )
    (net (code "126") (name "FP-CLK0L") (class "Default")
      (node (ref "IC34") (pin "3") (pinfunction "Y4_3") (pintype "tri_state"))
      (node (ref "JP6") (pin "25") (pinfunction "25_25") (pintype "passive"))
    )
    (net (code "127") (name "FP-CLK1H") (class "Default")
      (node (ref "IC34") (pin "9") (pinfunction "Y1_9") (pintype "tri_state"))
      (node (ref "JP6") (pin "19") (pinfunction "19_19") (pintype "passive"))
    )
    (net (code "128") (name "FP-CLK1L") (class "Default")
      (node (ref "IC34") (pin "7") (pinfunction "Y2_7") (pintype "tri_state"))
      (node (ref "JP6") (pin "21") (pinfunction "21_21") (pintype "passive"))
    )
    (net (code "129") (name "FP-CLK2H") (class "Default")
      (node (ref "IC33") (pin "16") (pinfunction "Y2_16") (pintype "tri_state"))
      (node (ref "JP6") (pin "24") (pinfunction "24_24") (pintype "passive"))
    )
    (net (code "130") (name "FP-CLK2L") (class "Default")
      (node (ref "IC33") (pin "18") (pinfunction "Y1_18") (pintype "tri_state"))
      (node (ref "JP6") (pin "26") (pinfunction "26_26") (pintype "passive"))
    )
    (net (code "131") (name "FP-CLK3H") (class "Default")
      (node (ref "IC33") (pin "12") (pinfunction "Y4_12") (pintype "tri_state"))
      (node (ref "JP6") (pin "20") (pinfunction "20_20") (pintype "passive"))
    )
    (net (code "132") (name "FP-CLK3L") (class "Default")
      (node (ref "IC33") (pin "14") (pinfunction "Y3_14") (pintype "tri_state"))
      (node (ref "JP6") (pin "22") (pinfunction "22_22") (pintype "passive"))
    )
    (net (code "133") (name "FP-CLK4H") (class "Default")
      (node (ref "IC34") (pin "14") (pinfunction "Y3_14") (pintype "tri_state"))
      (node (ref "JP6") (pin "31") (pinfunction "31_31") (pintype "passive"))
    )
    (net (code "134") (name "FP-CLK4L") (class "Default")
      (node (ref "IC34") (pin "12") (pinfunction "Y4_12") (pintype "tri_state"))
      (node (ref "JP6") (pin "33") (pinfunction "33_33") (pintype "passive"))
    )
    (net (code "135") (name "FP-CLK5H") (class "Default")
      (node (ref "IC34") (pin "18") (pinfunction "Y1_18") (pintype "tri_state"))
      (node (ref "JP6") (pin "27") (pinfunction "27_27") (pintype "passive"))
    )
    (net (code "136") (name "FP-CLK5L") (class "Default")
      (node (ref "IC34") (pin "16") (pinfunction "Y2_16") (pintype "tri_state"))
      (node (ref "JP6") (pin "29") (pinfunction "29_29") (pintype "passive"))
    )
    (net (code "137") (name "FP-CLK6H") (class "Default")
      (node (ref "IC33") (pin "7") (pinfunction "Y2_7") (pintype "tri_state"))
      (node (ref "JP6") (pin "32") (pinfunction "32_32") (pintype "passive"))
    )
    (net (code "138") (name "FP-CLK6L") (class "Default")
      (node (ref "IC33") (pin "9") (pinfunction "Y1_9") (pintype "tri_state"))
      (node (ref "JP6") (pin "34") (pinfunction "34_34") (pintype "passive"))
    )
    (net (code "139") (name "FP-CLK7H") (class "Default")
      (node (ref "IC33") (pin "3") (pinfunction "Y4_3") (pintype "tri_state"))
      (node (ref "JP6") (pin "28") (pinfunction "28_28") (pintype "passive"))
    )
    (net (code "140") (name "FP-CLK7L") (class "Default")
      (node (ref "IC33") (pin "5") (pinfunction "Y3_5") (pintype "tri_state"))
      (node (ref "JP6") (pin "30") (pinfunction "30_30") (pintype "passive"))
    )
    (net (code "141") (name "GND") (class "Default")
      (node (ref "C1") (pin "2") (pinfunction "2_2") (pintype "passive"))
      (node (ref "C10") (pin "2") (pinfunction "2_2") (pintype "passive"))
      (node (ref "C11") (pin "2") (pinfunction "2_2") (pintype "passive"))
      (node (ref "C12") (pin "2") (pinfunction "2_2") (pintype "passive"))
      (node (ref "C13") (pin "2") (pinfunction "2_2") (pintype "passive"))
      (node (ref "C14") (pin "2") (pinfunction "2_2") (pintype "passive"))
      (node (ref "C15") (pin "2") (pinfunction "2_2") (pintype "passive"))
      (node (ref "C16") (pin "2") (pinfunction "2_2") (pintype "passive"))
      (node (ref "C17") (pin "2") (pinfunction "2_2") (pintype "passive"))
      (node (ref "C18") (pin "2") (pinfunction "2_2") (pintype "passive"))
      (node (ref "C19") (pin "2") (pinfunction "2_2") (pintype "passive"))
      (node (ref "C2") (pin "2") (pinfunction "2_2") (pintype "passive"))
      (node (ref "C20") (pin "2") (pinfunction "2_2") (pintype "passive"))
      (node (ref "C21") (pin "2") (pinfunction "2_2") (pintype "passive"))
      (node (ref "C22") (pin "2") (pinfunction "2_2") (pintype "passive"))
      (node (ref "C23") (pin "2") (pinfunction "2_2") (pintype "passive"))
      (node (ref "C24") (pin "2") (pinfunction "2_2") (pintype "passive"))
      (node (ref "C25") (pin "2") (pinfunction "2_2") (pintype "passive"))
      (node (ref "C26") (pin "2") (pinfunction "2_2") (pintype "passive"))
      (node (ref "C27") (pin "2") (pinfunction "2_2") (pintype "passive"))
      (node (ref "C28") (pin "2") (pinfunction "2_2") (pintype "passive"))
      (node (ref "C29") (pin "2") (pinfunction "2_2") (pintype "passive"))
      (node (ref "C3") (pin "2") (pinfunction "2_2") (pintype "passive"))
      (node (ref "C30") (pin "2") (pinfunction "2_2") (pintype "passive"))
      (node (ref "C31") (pin "2") (pinfunction "2_2") (pintype "passive"))
      (node (ref "C32") (pin "2") (pinfunction "2_2") (pintype "passive"))
      (node (ref "C33") (pin "2") (pinfunction "2_2") (pintype "passive"))
      (node (ref "C34") (pin "2") (pinfunction "2_2") (pintype "passive"))
      (node (ref "C35") (pin "2") (pinfunction "2_2") (pintype "passive"))
      (node (ref "C36") (pin "2") (pinfunction "2_2") (pintype "passive"))
      (node (ref "C37") (pin "2") (pinfunction "2_2") (pintype "passive"))
      (node (ref "C4") (pin "2") (pinfunction "2_2") (pintype "passive"))
      (node (ref "C5") (pin "2") (pinfunction "2_2") (pintype "passive"))
      (node (ref "C6") (pin "2") (pinfunction "2_2") (pintype "passive"))
      (node (ref "C7") (pin "2") (pinfunction "2_2") (pintype "passive"))
      (node (ref "C8") (pin "2") (pinfunction "2_2") (pintype "passive"))
      (node (ref "C9") (pin "2") (pinfunction "2_2") (pintype "passive"))
      (node (ref "IC5") (pin "10") (pinfunction "I1_10") (pintype "input"))
      (node (ref "IC5") (pin "12") (pinfunction "I0_12") (pintype "input"))
      (node (ref "IC5") (pin "13") (pinfunction "I1_13") (pintype "input"))
      (node (ref "IC5") (pin "4") (pinfunction "I0_4") (pintype "input"))
      (node (ref "IC5") (pin "5") (pinfunction "I1_5") (pintype "input"))
      (node (ref "IC5") (pin "9") (pinfunction "I0_9") (pintype "input"))
      (node (ref "J1") (pin "2") (pinfunction "2_2") (pintype "passive"))
      (node (ref "JP6") (pin "39") (pinfunction "39_39") (pintype "passive"))
      (node (ref "JP6") (pin "40") (pinfunction "40_40") (pintype "passive"))
      (node (ref "PWR") (pin "K") (pinfunction "C_K") (pintype "passive"))
      (node (ref "X1") (pin "A1") (pinfunction "B_A1") (pintype "passive"))
      (node (ref "X1") (pin "A32") (pinfunction "B_A32") (pintype "passive"))
      (node (ref "X1") (pin "B1") (pinfunction "B_B1") (pintype "passive"))
      (node (ref "X1") (pin "B32") (pinfunction "B_B32") (pintype "passive"))
      (node (ref "X1") (pin "C1") (pinfunction "B_C1") (pintype "passive"))
      (node (ref "X1") (pin "C32") (pinfunction "B_C32") (pintype "passive"))
    )
    (net (code "142") (name "H{slash}L-SWAP") (class "Default")
      (node (ref "IC1") (pin "13") (pinfunction "I_13") (pintype "input"))
      (node (ref "IC6") (pin "10") (pinfunction "I1_10") (pintype "input"))
      (node (ref "X1") (pin "C25") (pinfunction "B_C25") (pintype "passive"))
    )
    (net (code "143") (name "IN") (class "Default")
      (node (ref "X1") (pin "C26") (pinfunction "B_C26") (pintype "passive"))
    )
    (net (code "144") (name "INT") (class "Default")
      (node (ref "X1") (pin "B29") (pinfunction "B_B29") (pintype "passive"))
    )
    (net (code "145") (name "INTA") (class "Default")
      (node (ref "X1") (pin "B30") (pinfunction "B_B30") (pintype "passive"))
    )
    (net (code "146") (name "I{slash}O-ADDR") (class "Default")
      (node (ref "X1") (pin "B28") (pinfunction "B_B28") (pintype "passive"))
    )
    (net (code "147") (name "I{slash}O-RD") (class "Default")
      (node (ref "X1") (pin "B27") (pinfunction "B_B27") (pintype "passive"))
    )
    (net (code "148") (name "I{slash}O-WR") (class "Default")
      (node (ref "X1") (pin "B26") (pinfunction "B_B26") (pintype "passive"))
    )
    (net (code "149") (name "MEM-RD") (class "Default")
      (node (ref "X1") (pin "B25") (pinfunction "B_B25") (pintype "passive"))
    )
    (net (code "150") (name "MEM-WR") (class "Default")
      (node (ref "X1") (pin "B24") (pinfunction "B_B24") (pintype "passive"))
    )
    (net (code "151") (name "Net-(IC1F-O)") (class "Default")
      (node (ref "IC1") (pin "12") (pinfunction "O_12") (pintype "output"))
      (node (ref "IC6") (pin "1") (pinfunction "I0_1") (pintype "input"))
    )
    (net (code "152") (name "Net-(IC2A-G1)") (class "Default")
      (node (ref "IC2") (pin "6") (pinfunction "G1_6") (pintype "input"))
      (node (ref "IC3") (pin "6") (pinfunction "G1_6") (pintype "input"))
      (node (ref "R2") (pin "1") (pinfunction "1_1") (pintype "passive"))
    )
    (net (code "153") (name "Net-(IC4A-O)") (class "Default")
      (node (ref "IC4") (pin "3") (pinfunction "O_3") (pintype "output"))
      (node (ref "IC4") (pin "4") (pinfunction "I0_4") (pintype "input"))
    )
    (net (code "154") (name "Net-(IC4B-O)") (class "Default")
      (node (ref "IC4") (pin "6") (pinfunction "O_6") (pintype "output"))
      (node (ref "JP1") (pin "1") (pinfunction "1_1") (pintype "passive"))
    )
    (net (code "155") (name "Net-(IC4C-O)") (class "Default")
      (node (ref "IC4") (pin "8") (pinfunction "O_8") (pintype "output"))
      (node (ref "JP1") (pin "3") (pinfunction "3_3") (pintype "passive"))
    )
    (net (code "156") (name "Net-(IC4D-I0)") (class "Default")
      (node (ref "IC4") (pin "12") (pinfunction "I0_12") (pintype "input"))
      (node (ref "IC6") (pin "11") (pinfunction "O_11") (pintype "output"))
    )
    (net (code "157") (name "Net-(IC4D-O)") (class "Default")
      (node (ref "IC4") (pin "11") (pinfunction "O_11") (pintype "output"))
      (node (ref "JP2") (pin "1") (pinfunction "1_1") (pintype "passive"))
    )
    (net (code "158") (name "Net-(IC5A-O)") (class "Default")
      (node (ref "IC5") (pin "3") (pinfunction "O_3") (pintype "output"))
      (node (ref "IC6") (pin "2") (pinfunction "I1_2") (pintype "input"))
      (node (ref "IC6") (pin "9") (pinfunction "I0_9") (pintype "input"))
    )
    (net (code "159") (name "Net-(IC6A-O)") (class "Default")
      (node (ref "IC6") (pin "3") (pinfunction "O_3") (pintype "output"))
      (node (ref "IC7") (pin "19") (pinfunction "G_19") (pintype "input"))
      (node (ref "IC8") (pin "19") (pinfunction "G_19") (pintype "input"))
    )
    (net (code "160") (name "Net-(IC6B-O)") (class "Default")
      (node (ref "IC6") (pin "6") (pinfunction "O_6") (pintype "output"))
      (node (ref "JP2") (pin "3") (pinfunction "3_3") (pintype "passive"))
    )
    (net (code "161") (name "Net-(IC6C-O)") (class "Default")
      (node (ref "IC6") (pin "8") (pinfunction "O_8") (pintype "output"))
      (node (ref "IC9") (pin "19") (pinfunction "G_19") (pintype "input"))
    )
    (net (code "162") (name "Net-(IC10A-OC)") (class "Default")
      (node (ref "IC10") (pin "1") (pinfunction "OC_1") (pintype "input"))
      (node (ref "IC32") (pin "3") (pinfunction "O_3") (pintype "output"))
    )
    (net (code "163") (name "Net-(IC11A-G)") (class "Default")
      (node (ref "IC11") (pin "1") (pinfunction "G_1") (pintype "input"))
      (node (ref "IC11") (pin "19") (pinfunction "G_19") (pintype "input"))
      (node (ref "IC12") (pin "1") (pinfunction "G_1") (pintype "input"))
      (node (ref "IC12") (pin "19") (pinfunction "G_19") (pintype "input"))
      (node (ref "IC33") (pin "1") (pinfunction "G_1") (pintype "input"))
      (node (ref "IC33") (pin "19") (pinfunction "G_19") (pintype "input"))
      (node (ref "IC34") (pin "1") (pinfunction "G_1") (pintype "input"))
      (node (ref "IC34") (pin "19") (pinfunction "G_19") (pintype "input"))
      (node (ref "J1") (pin "1") (pinfunction "1_1") (pintype "passive"))
      (node (ref "R1") (pin "1") (pinfunction "1_1") (pintype "passive"))
    )
    (net (code "164") (name "Net-(IC13A-O)") (class "Default")
      (node (ref "IC13") (pin "3") (pinfunction "O_3") (pintype "output"))
      (node (ref "IC15") (pin "1") (pinfunction "OC_1") (pintype "input"))
    )
    (net (code "165") (name "Net-(IC13B-O)") (class "Default")
      (node (ref "IC13") (pin "6") (pinfunction "O_6") (pintype "output"))
      (node (ref "IC16") (pin "1") (pinfunction "OC_1") (pintype "input"))
    )
    (net (code "166") (name "Net-(IC13C-O)") (class "Default")
      (node (ref "IC13") (pin "8") (pinfunction "O_8") (pintype "output"))
      (node (ref "IC17") (pin "1") (pinfunction "OC_1") (pintype "input"))
    )
    (net (code "167") (name "Net-(IC13D-O)") (class "Default")
      (node (ref "IC13") (pin "11") (pinfunction "O_11") (pintype "output"))
      (node (ref "IC18") (pin "1") (pinfunction "OC_1") (pintype "input"))
    )
    (net (code "168") (name "Net-(IC19A-O)") (class "Default")
      (node (ref "IC19") (pin "3") (pinfunction "O_3") (pintype "output"))
      (node (ref "IC21") (pin "1") (pinfunction "OC_1") (pintype "input"))
    )
    (net (code "169") (name "Net-(IC19B-O)") (class "Default")
      (node (ref "IC19") (pin "6") (pinfunction "O_6") (pintype "output"))
      (node (ref "IC22") (pin "1") (pinfunction "OC_1") (pintype "input"))
    )
    (net (code "170") (name "Net-(IC19C-O)") (class "Default")
      (node (ref "IC19") (pin "8") (pinfunction "O_8") (pintype "output"))
      (node (ref "IC23") (pin "1") (pinfunction "OC_1") (pintype "input"))
    )
    (net (code "171") (name "Net-(IC19D-O)") (class "Default")
      (node (ref "IC19") (pin "11") (pinfunction "O_11") (pintype "output"))
      (node (ref "IC24") (pin "1") (pinfunction "OC_1") (pintype "input"))
    )
    (net (code "172") (name "Net-(IC25A-OC)") (class "Default")
      (node (ref "IC25") (pin "1") (pinfunction "OC_1") (pintype "input"))
      (node (ref "IC32") (pin "6") (pinfunction "O_6") (pintype "output"))
    )
    (net (code "173") (name "Net-(IC26A-OC)") (class "Default")
      (node (ref "IC26") (pin "1") (pinfunction "OC_1") (pintype "input"))
      (node (ref "IC37") (pin "3") (pinfunction "O_3") (pintype "output"))
    )
    (net (code "174") (name "Net-(IC27A-OC)") (class "Default")
      (node (ref "IC27") (pin "1") (pinfunction "OC_1") (pintype "input"))
      (node (ref "IC37") (pin "6") (pinfunction "O_6") (pintype "output"))
    )
    (net (code "175") (name "Net-(IC28A-OC)") (class "Default")
      (node (ref "IC28") (pin "1") (pinfunction "OC_1") (pintype "input"))
      (node (ref "IC32") (pin "8") (pinfunction "O_8") (pintype "output"))
    )
    (net (code "176") (name "Net-(IC29A-OC)") (class "Default")
      (node (ref "IC29") (pin "1") (pinfunction "OC_1") (pintype "input"))
      (node (ref "IC32") (pin "11") (pinfunction "O_11") (pintype "output"))
    )
    (net (code "177") (name "Net-(IC30A-OC)") (class "Default")
      (node (ref "IC30") (pin "1") (pinfunction "OC_1") (pintype "input"))
      (node (ref "IC37") (pin "8") (pinfunction "O_8") (pintype "output"))
    )
    (net (code "178") (name "Net-(IC31A-OC)") (class "Default")
      (node (ref "IC31") (pin "1") (pinfunction "OC_1") (pintype "input"))
      (node (ref "IC37") (pin "11") (pinfunction "O_11") (pintype "output"))
    )
    (net (code "179") (name "Net-(PWR-PadA)") (class "Default")
      (node (ref "PWR") (pin "A") (pinfunction "A_A") (pintype "passive"))
      (node (ref "R3") (pin "1") (pinfunction "1_1") (pintype "passive"))
    )
    (net (code "180") (name "OUT") (class "Default")
      (node (ref "X1") (pin "C27") (pinfunction "B_C27") (pintype "passive"))
    )
    (net (code "181") (name "REG-BRD-LD-ID") (class "Default")
      (node (ref "IC6") (pin "12") (pinfunction "I0_12") (pintype "input"))
      (node (ref "IC6") (pin "13") (pinfunction "I1_13") (pintype "input"))
      (node (ref "IC6") (pin "5") (pinfunction "I1_5") (pintype "input"))
      (node (ref "X1") (pin "B16") (pinfunction "B_B16") (pintype "passive"))
    )
    (net (code "182") (name "REG-BRD-RD-ID") (class "Default")
      (node (ref "IC4") (pin "1") (pinfunction "I0_1") (pintype "input"))
      (node (ref "IC4") (pin "10") (pinfunction "I1_10") (pintype "input"))
      (node (ref "IC4") (pin "2") (pinfunction "I1_2") (pintype "input"))
      (node (ref "X1") (pin "B12") (pinfunction "B_B12") (pintype "passive"))
    )
    (net (code "183") (name "REG-FUNC-LD") (class "Default")
      (node (ref "IC4") (pin "13") (pinfunction "I1_13") (pintype "input"))
      (node (ref "IC6") (pin "4") (pinfunction "I0_4") (pintype "input"))
      (node (ref "X1") (pin "B7") (pinfunction "B_B7") (pintype "passive"))
    )
    (net (code "184") (name "REG-FUNC-RD") (class "Default")
      (node (ref "IC4") (pin "5") (pinfunction "I1_5") (pintype "input"))
      (node (ref "IC4") (pin "9") (pinfunction "I0_9") (pintype "input"))
      (node (ref "X1") (pin "B8") (pinfunction "B_B8") (pintype "passive"))
    )
    (net (code "185") (name "REG-LD-HI") (class "Default")
      (node (ref "IC1") (pin "9") (pinfunction "I_9") (pintype "input"))
      (node (ref "X1") (pin "B23") (pinfunction "B_B23") (pintype "passive"))
    )
    (net (code "186") (name "REG-LD-ID0") (class "Default")
      (node (ref "IC3") (pin "1") (pinfunction "A_1") (pintype "input"))
      (node (ref "X1") (pin "B17") (pinfunction "B_B17") (pintype "passive"))
    )
    (net (code "187") (name "REG-LD-ID1") (class "Default")
      (node (ref "IC3") (pin "2") (pinfunction "B_2") (pintype "input"))
      (node (ref "X1") (pin "B18") (pinfunction "B_B18") (pintype "passive"))
    )
    (net (code "188") (name "REG-LD-ID2") (class "Default")
      (node (ref "IC3") (pin "3") (pinfunction "C_3") (pintype "input"))
      (node (ref "X1") (pin "B19") (pinfunction "B_B19") (pintype "passive"))
    )
    (net (code "189") (name "REG-LD-LO") (class "Default")
      (node (ref "IC1") (pin "3") (pinfunction "I_3") (pintype "input"))
      (node (ref "X1") (pin "B21") (pinfunction "B_B21") (pintype "passive"))
    )
    (net (code "190") (name "REG-RD-HI") (class "Default")
      (node (ref "IC1") (pin "5") (pinfunction "I_5") (pintype "input"))
      (node (ref "X1") (pin "B22") (pinfunction "B_B22") (pintype "passive"))
    )
    (net (code "191") (name "REG-RD-ID0") (class "Default")
      (node (ref "IC2") (pin "1") (pinfunction "A_1") (pintype "input"))
      (node (ref "X1") (pin "B13") (pinfunction "B_B13") (pintype "passive"))
    )
    (net (code "192") (name "REG-RD-ID1") (class "Default")
      (node (ref "IC2") (pin "2") (pinfunction "B_2") (pintype "input"))
      (node (ref "X1") (pin "B14") (pinfunction "B_B14") (pintype "passive"))
    )
    (net (code "193") (name "REG-RD-ID2") (class "Default")
      (node (ref "IC2") (pin "3") (pinfunction "C_3") (pintype "input"))
      (node (ref "X1") (pin "B15") (pinfunction "B_B15") (pintype "passive"))
    )
    (net (code "194") (name "REG-RD-LO") (class "Default")
      (node (ref "IC1") (pin "1") (pinfunction "I_1") (pintype "input"))
      (node (ref "X1") (pin "B20") (pinfunction "B_B20") (pintype "passive"))
    )
    (net (code "195") (name "RESET") (class "Default")
      (node (ref "X1") (pin "C30") (pinfunction "B_C30") (pintype "passive"))
    )
    (net (code "196") (name "RUN") (class "Default")
      (node (ref "X1") (pin "C29") (pinfunction "B_C29") (pintype "passive"))
    )
    (net (code "197") (name "SR-LD") (class "Default")
      (node (ref "X1") (pin "C23") (pinfunction "B_C23") (pintype "passive"))
    )
    (net (code "198") (name "TMP-REG-LD") (class "Default")
      (node (ref "X1") (pin "C3") (pinfunction "B_C3") (pintype "passive"))
    )
    (net (code "199") (name "TMP-REG-RD") (class "Default")
      (node (ref "X1") (pin "C4") (pinfunction "B_C4") (pintype "passive"))
    )
    (net (code "200") (name "UNUSED1") (class "Default")
      (node (ref "X1") (pin "B11") (pinfunction "B_B11") (pintype "passive"))
    )
    (net (code "201") (name "UNUSED2") (class "Default")
      (node (ref "X1") (pin "C5") (pinfunction "B_C5") (pintype "passive"))
    )
    (net (code "202") (name "VCC") (class "Default")
      (node (ref "C1") (pin "1") (pinfunction "1_1") (pintype "passive"))
      (node (ref "C10") (pin "1") (pinfunction "1_1") (pintype "passive"))
      (node (ref "C11") (pin "1") (pinfunction "1_1") (pintype "passive"))
      (node (ref "C12") (pin "1") (pinfunction "1_1") (pintype "passive"))
      (node (ref "C13") (pin "1") (pinfunction "1_1") (pintype "passive"))
      (node (ref "C14") (pin "1") (pinfunction "1_1") (pintype "passive"))
      (node (ref "C15") (pin "1") (pinfunction "1_1") (pintype "passive"))
      (node (ref "C16") (pin "1") (pinfunction "1_1") (pintype "passive"))
      (node (ref "C17") (pin "1") (pinfunction "1_1") (pintype "passive"))
      (node (ref "C18") (pin "1") (pinfunction "1_1") (pintype "passive"))
      (node (ref "C19") (pin "1") (pinfunction "1_1") (pintype "passive"))
      (node (ref "C2") (pin "1") (pinfunction "1_1") (pintype "passive"))
      (node (ref "C20") (pin "1") (pinfunction "1_1") (pintype "passive"))
      (node (ref "C21") (pin "1") (pinfunction "1_1") (pintype "passive"))
      (node (ref "C22") (pin "1") (pinfunction "1_1") (pintype "passive"))
      (node (ref "C23") (pin "1") (pinfunction "1_1") (pintype "passive"))
      (node (ref "C24") (pin "1") (pinfunction "1_1") (pintype "passive"))
      (node (ref "C25") (pin "1") (pinfunction "1_1") (pintype "passive"))
      (node (ref "C26") (pin "1") (pinfunction "1_1") (pintype "passive"))
      (node (ref "C27") (pin "1") (pinfunction "1_1") (pintype "passive"))
      (node (ref "C28") (pin "1") (pinfunction "1_1") (pintype "passive"))
      (node (ref "C29") (pin "1") (pinfunction "1_1") (pintype "passive"))
      (node (ref "C3") (pin "1") (pinfunction "1_1") (pintype "passive"))
      (node (ref "C30") (pin "1") (pinfunction "1_1") (pintype "passive"))
      (node (ref "C31") (pin "1") (pinfunction "1_1") (pintype "passive"))
      (node (ref "C32") (pin "1") (pinfunction "1_1") (pintype "passive"))
      (node (ref "C33") (pin "1") (pinfunction "1_1") (pintype "passive"))
      (node (ref "C34") (pin "1") (pinfunction "1_1") (pintype "passive"))
      (node (ref "C35") (pin "1") (pinfunction "1_1") (pintype "passive"))
      (node (ref "C36") (pin "1") (pinfunction "1_1") (pintype "passive"))
      (node (ref "C37") (pin "1") (pinfunction "1_1") (pintype "passive"))
      (node (ref "C4") (pin "1") (pinfunction "1_1") (pintype "passive"))
      (node (ref "C5") (pin "1") (pinfunction "1_1") (pintype "passive"))
      (node (ref "C6") (pin "1") (pinfunction "1_1") (pintype "passive"))
      (node (ref "C7") (pin "1") (pinfunction "1_1") (pintype "passive"))
      (node (ref "C8") (pin "1") (pinfunction "1_1") (pintype "passive"))
      (node (ref "C9") (pin "1") (pinfunction "1_1") (pintype "passive"))
      (node (ref "JP6") (pin "1") (pinfunction "1_1") (pintype "passive"))
      (node (ref "JP6") (pin "2") (pinfunction "2_2") (pintype "passive"))
      (node (ref "R1") (pin "2") (pinfunction "2_2") (pintype "passive"))
      (node (ref "R2") (pin "2") (pinfunction "2_2") (pintype "passive"))
      (node (ref "R3") (pin "2") (pinfunction "2_2") (pintype "passive"))
      (node (ref "RN1") (pin "1") (pinfunction "1_1") (pintype "passive"))
      (node (ref "RN2") (pin "1") (pinfunction "1_1") (pintype "passive"))
      (node (ref "X1") (pin "A2") (pinfunction "B_A2") (pintype "passive"))
      (node (ref "X1") (pin "A31") (pinfunction "B_A31") (pintype "passive"))
      (node (ref "X1") (pin "B2") (pinfunction "B_B2") (pintype "passive"))
      (node (ref "X1") (pin "B31") (pinfunction "B_B31") (pintype "passive"))
      (node (ref "X1") (pin "C2") (pinfunction "B_C2") (pintype "passive"))
      (node (ref "X1") (pin "C31") (pinfunction "B_C31") (pintype "passive"))
    )
    (net (code "203") (name "unconnected-(IC5B-O-Pad6)") (class "Default")
      (node (ref "IC5") (pin "6") (pinfunction "O_6") (pintype "output"))
    )
    (net (code "204") (name "unconnected-(IC5C-O-Pad8)") (class "Default")
      (node (ref "IC5") (pin "8") (pinfunction "O_8") (pintype "output"))
    )
    (net (code "205") (name "unconnected-(IC5D-O-Pad11)") (class "Default")
      (node (ref "IC5") (pin "11") (pinfunction "O_11") (pintype "output"))
    )
    (net (code "206") (name "unconnected-(JP6-Pad35)") (class "Default")
      (node (ref "JP6") (pin "35") (pinfunction "35_35") (pintype "passive"))
    )
    (net (code "207") (name "unconnected-(JP6-Pad36)") (class "Default")
      (node (ref "JP6") (pin "36") (pinfunction "36_36") (pintype "passive"))
    )
    (net (code "208") (name "unconnected-(JP6-Pad37)") (class "Default")
      (node (ref "JP6") (pin "37") (pinfunction "37_37") (pintype "passive"))
    )
    (net (code "209") (name "unconnected-(JP6-Pad38)") (class "Default")
      (node (ref "JP6") (pin "38") (pinfunction "38_38") (pintype "passive"))
    )
  )
)
